# HLK-7621-ALL-KIT-V2_2.net
KiCad netlist of a schematic drawn in Altium Designer
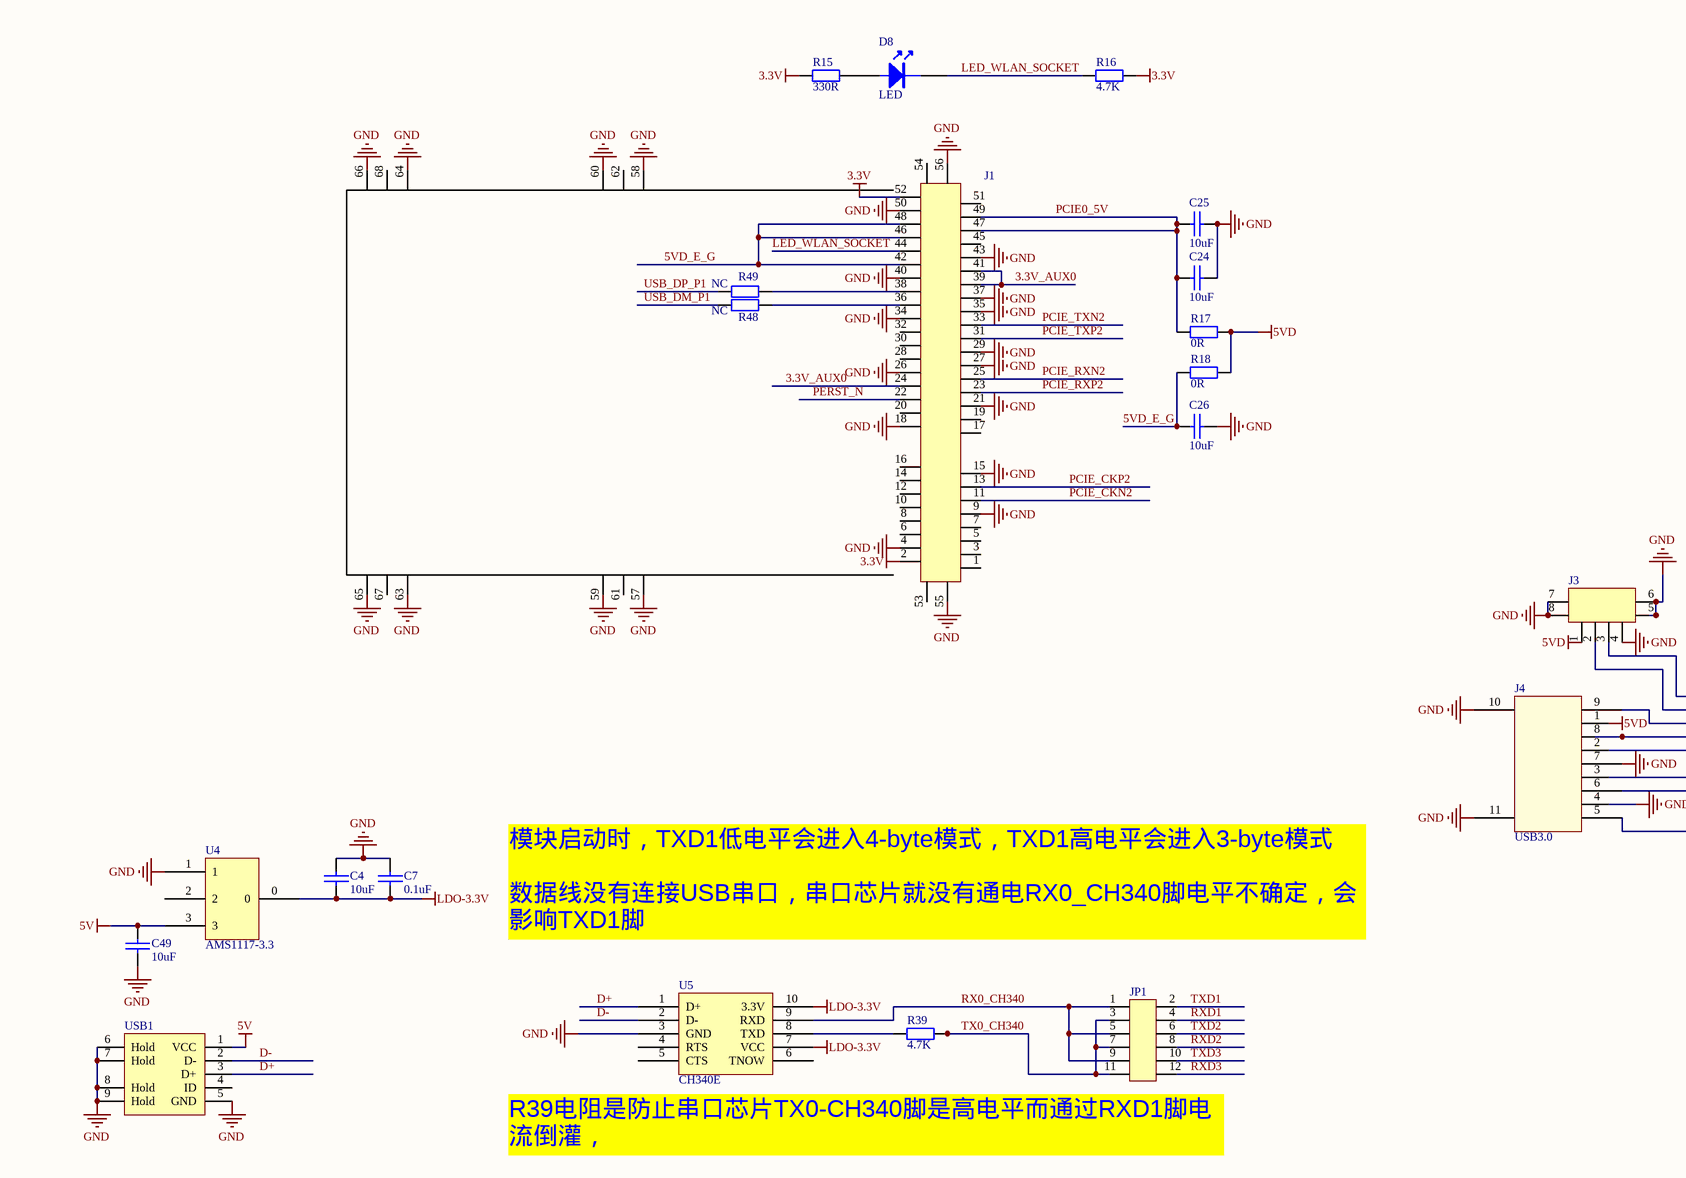
[diagram p0: HLK-7621-ALL-KIT-V2.2.SchDoc, top left]
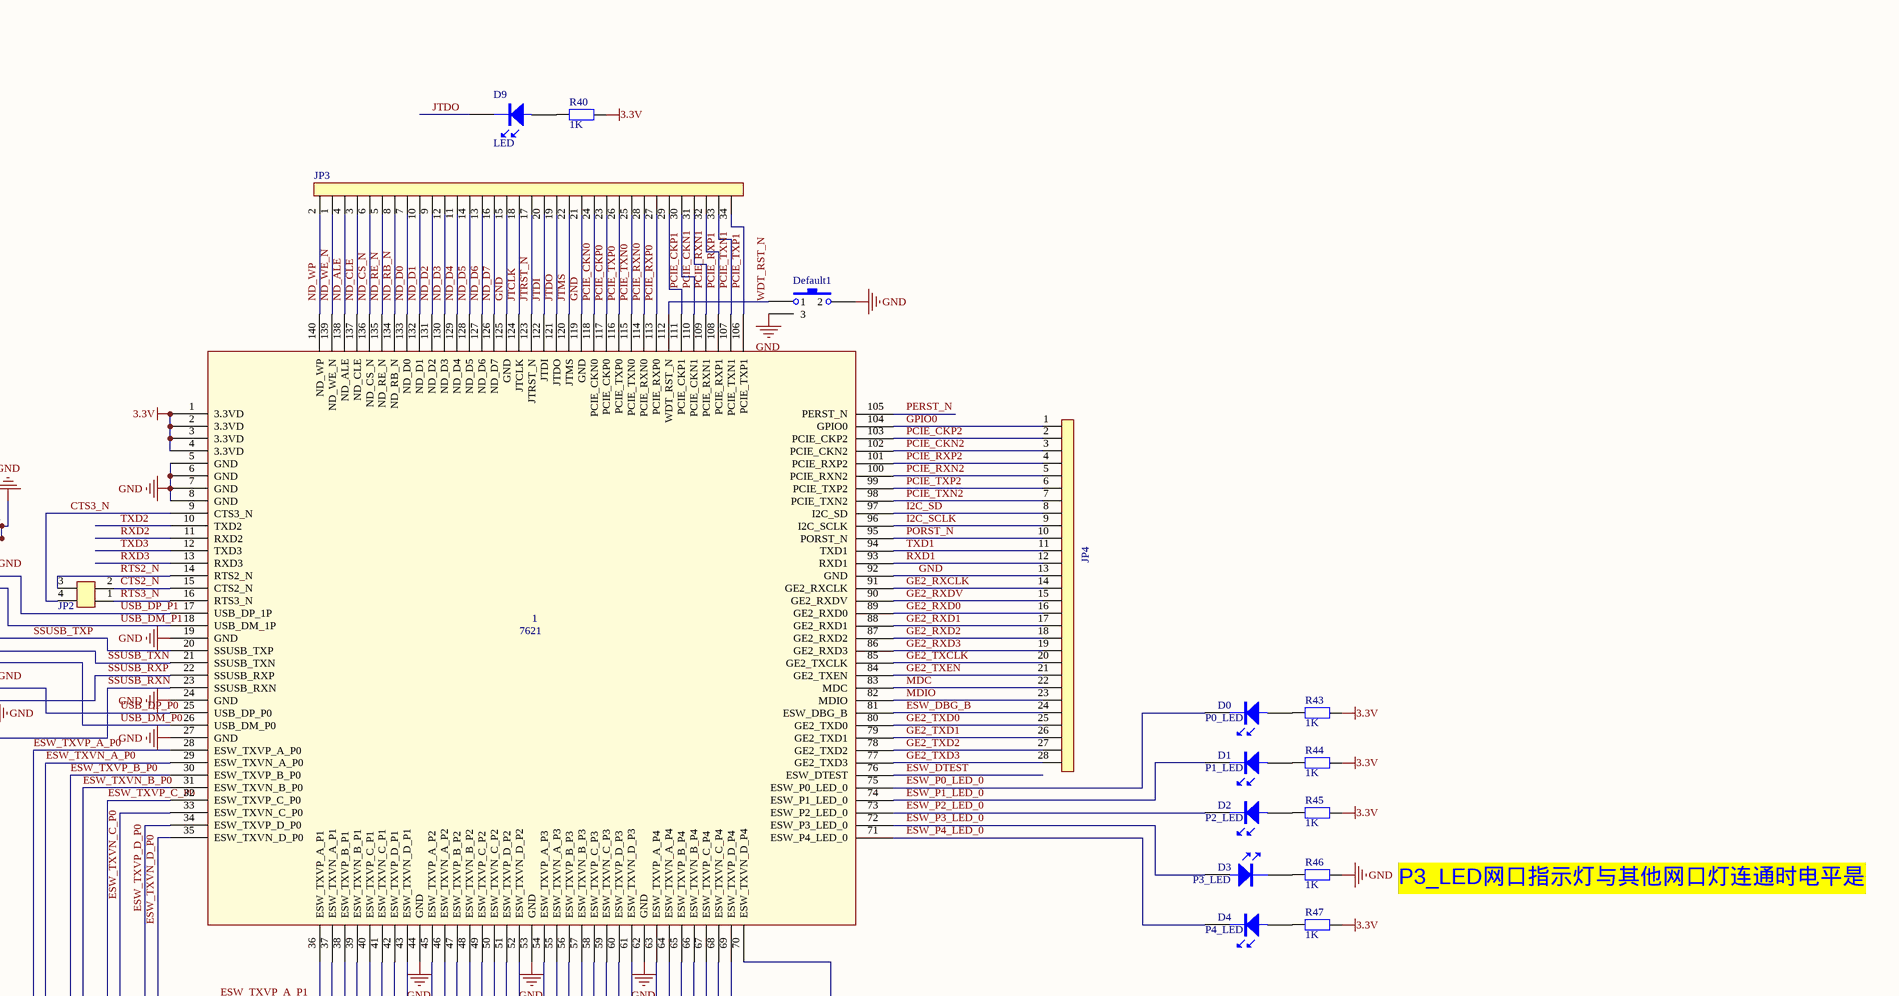
[diagram p1: HLK-7621-ALL-KIT-V2.2.SchDoc, top right]
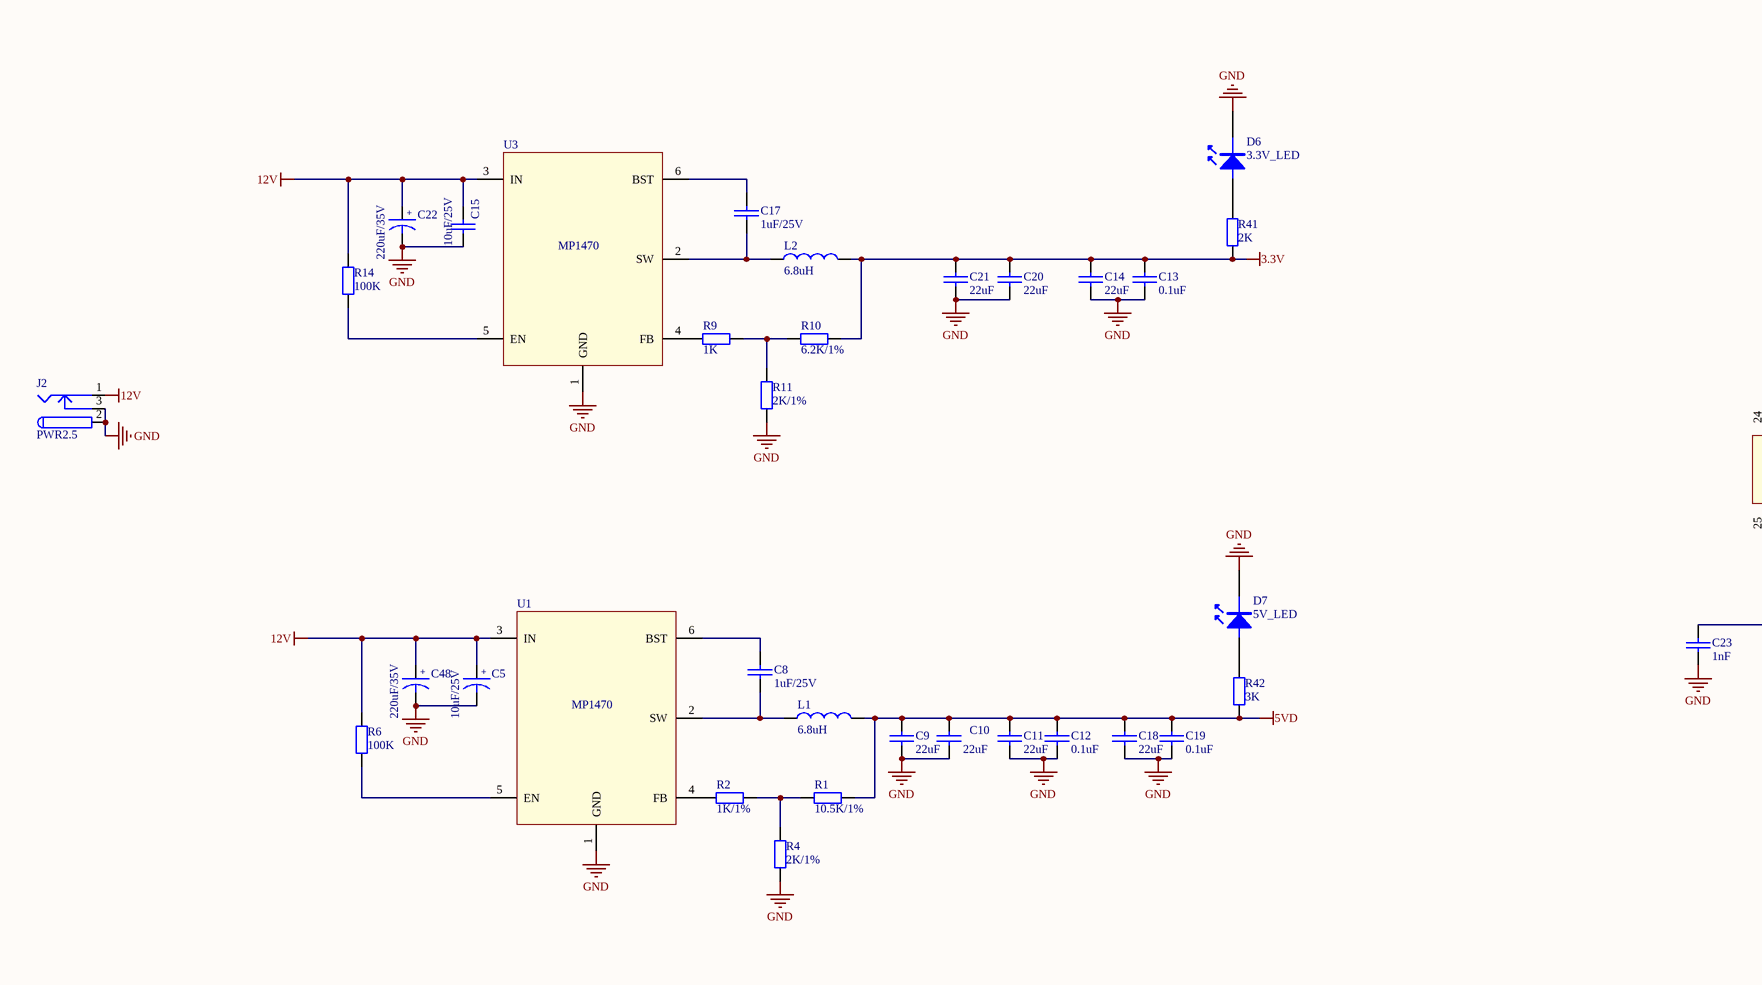
[diagram p2: HLK-7621-ALL-KIT-V2.2.SchDoc, bottom left]
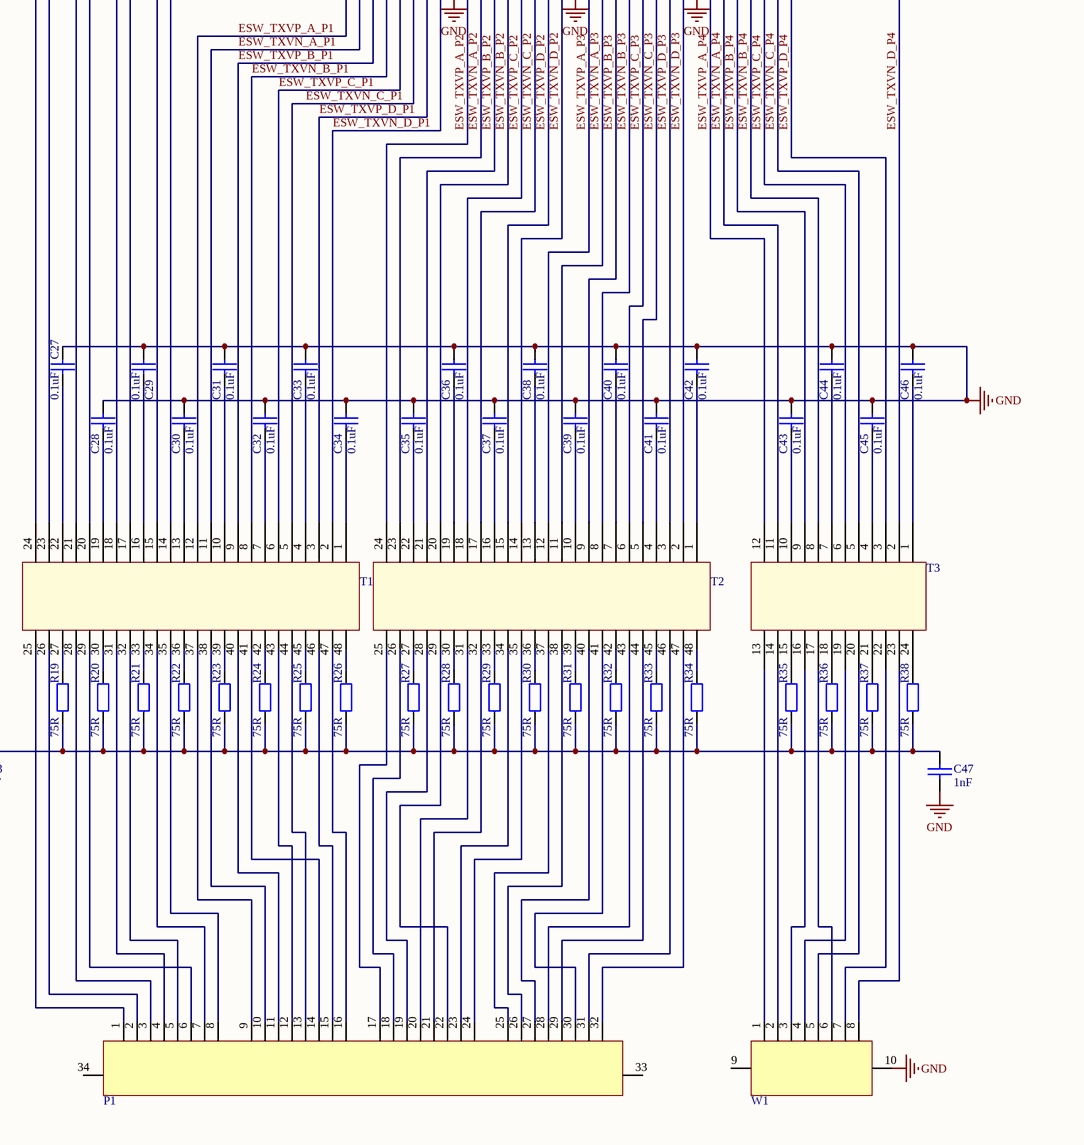
[diagram p3: HLK-7621-ALL-KIT-V2.2.SchDoc, bottom right]

(export (version "E")
  (design (tool "Eeschema 10.0.6"))
  (components
    (comp (ref "1") (value "7621") (footprint "HLK-7621") (libsource (lib "Schlib1") (part "7621")))
    (comp (ref "C4")
      (value "10uF")
      (footprint "0603")
      (description "Capacitor")
      (libsource (lib "*") (part "CAP"))
    )
    (comp (ref "C5")
      (value "10uF/25V")
      (footprint "L0805")
      (description "Capacitor")
      (libsource (lib "Miscellaneous Devices") (part "CAPACITOR POL"))
    )
    (comp (ref "C7")
      (value "0.1uF")
      (footprint "0603")
      (description "Capacitor")
      (libsource (lib "*") (part "CAP"))
    )
    (comp (ref "C8")
      (value "1uF/25V")
      (footprint "0603")
      (description "Capacitor")
      (libsource (lib "*") (part "CAP"))
    )
    (comp (ref "C9")
      (value "22uF")
      (footprint "0603")
      (description "Capacitor")
      (libsource (lib "*") (part "CAP"))
    )
    (comp (ref "C10")
      (value "22uF")
      (footprint "0603")
      (description "Capacitor")
      (libsource (lib "*") (part "CAP"))
    )
    (comp (ref "C11")
      (value "22uF")
      (footprint "0603")
      (description "Capacitor")
      (libsource (lib "*") (part "CAP"))
    )
    (comp (ref "C12")
      (value "0.1uF")
      (footprint "0603")
      (description "Capacitor")
      (libsource (lib "*") (part "CAP"))
    )
    (comp (ref "C13")
      (value "0.1uF")
      (footprint "0603")
      (description "Capacitor")
      (libsource (lib "*") (part "CAP"))
    )
    (comp (ref "C14")
      (value "22uF")
      (footprint "0603")
      (description "Capacitor")
      (libsource (lib "*") (part "CAP"))
    )
    (comp (ref "C15")
      (value "10uF/25V")
      (footprint "L0805")
      (description "Capacitor")
      (libsource (lib "*") (part "CAP"))
    )
    (comp (ref "C17")
      (value "1uF/25V")
      (footprint "0603")
      (description "Capacitor")
      (libsource (lib "*") (part "CAP"))
    )
    (comp (ref "C18")
      (value "22uF")
      (footprint "0603")
      (description "Capacitor")
      (libsource (lib "*") (part "CAP"))
    )
    (comp (ref "C19")
      (value "0.1uF")
      (footprint "0603")
      (description "Capacitor")
      (libsource (lib "*") (part "CAP"))
    )
    (comp (ref "C20")
      (value "22uF")
      (footprint "0603")
      (description "Capacitor")
      (libsource (lib "*") (part "CAP"))
    )
    (comp (ref "C21")
      (value "22uF")
      (footprint "0603")
      (description "Capacitor")
      (libsource (lib "*") (part "CAP"))
    )
    (comp (ref "C22")
      (value "220uF/35V")
      (footprint "CAP_SMT_8*10.5")
      (description "Capacitor")
      (libsource (lib "Miscellaneous Devices") (part "CAPACITOR POL"))
    )
    (comp (ref "C23")
      (value "1nF")
      (footprint "C1206")
      (description "Capacitor")
      (libsource (lib "*") (part "CAP"))
    )
    (comp (ref "C24")
      (value "10uF")
      (footprint "C1206")
      (description "Capacitor")
      (libsource (lib "*") (part "CAP"))
    )
    (comp (ref "C25")
      (value "10uF")
      (footprint "C1206")
      (description "Capacitor")
      (libsource (lib "*") (part "CAP"))
    )
    (comp (ref "C26")
      (value "10uF")
      (footprint "C1206")
      (description "Capacitor")
      (libsource (lib "*") (part "CAP"))
    )
    (comp (ref "C27")
      (value "0.1uF")
      (footprint "C0402")
      (description "Capacitor")
      (libsource (lib "*") (part "CAP"))
    )
    (comp (ref "C28")
      (value "0.1uF")
      (footprint "C0402")
      (description "Capacitor")
      (libsource (lib "*") (part "CAP"))
    )
    (comp (ref "C29")
      (value "0.1uF")
      (footprint "C0402")
      (description "Capacitor")
      (libsource (lib "*") (part "CAP"))
    )
    (comp (ref "C30")
      (value "0.1uF")
      (footprint "C0402")
      (description "Capacitor")
      (libsource (lib "*") (part "CAP"))
    )
    (comp (ref "C31")
      (value "0.1uF")
      (footprint "C0402")
      (description "Capacitor")
      (libsource (lib "*") (part "CAP"))
    )
    (comp (ref "C32")
      (value "0.1uF")
      (footprint "C0402")
      (description "Capacitor")
      (libsource (lib "*") (part "CAP"))
    )
    (comp (ref "C33")
      (value "0.1uF")
      (footprint "C0402")
      (description "Capacitor")
      (libsource (lib "*") (part "CAP"))
    )
    (comp (ref "C34")
      (value "0.1uF")
      (footprint "C0402")
      (description "Capacitor")
      (libsource (lib "*") (part "CAP"))
    )
    (comp (ref "C35")
      (value "0.1uF")
      (footprint "C0402")
      (description "Capacitor")
      (libsource (lib "*") (part "CAP"))
    )
    (comp (ref "C36")
      (value "0.1uF")
      (footprint "C0402")
      (description "Capacitor")
      (libsource (lib "*") (part "CAP"))
    )
    (comp (ref "C37")
      (value "0.1uF")
      (footprint "C0402")
      (description "Capacitor")
      (libsource (lib "*") (part "CAP"))
    )
    (comp (ref "C38")
      (value "0.1uF")
      (footprint "C0402")
      (description "Capacitor")
      (libsource (lib "*") (part "CAP"))
    )
    (comp (ref "C39")
      (value "0.1uF")
      (footprint "C0402")
      (description "Capacitor")
      (libsource (lib "*") (part "CAP"))
    )
    (comp (ref "C40")
      (value "0.1uF")
      (footprint "C0402")
      (description "Capacitor")
      (libsource (lib "*") (part "CAP"))
    )
    (comp (ref "C41")
      (value "0.1uF")
      (footprint "C0402")
      (description "Capacitor")
      (libsource (lib "*") (part "CAP"))
    )
    (comp (ref "C42")
      (value "0.1uF")
      (footprint "C0402")
      (description "Capacitor")
      (libsource (lib "*") (part "CAP"))
    )
    (comp (ref "C43")
      (value "0.1uF")
      (footprint "C0402")
      (description "Capacitor")
      (libsource (lib "*") (part "CAP"))
    )
    (comp (ref "C44")
      (value "0.1uF")
      (footprint "C0402")
      (description "Capacitor")
      (libsource (lib "*") (part "CAP"))
    )
    (comp (ref "C45")
      (value "0.1uF")
      (footprint "C0402")
      (description "Capacitor")
      (libsource (lib "*") (part "CAP"))
    )
    (comp (ref "C46")
      (value "0.1uF")
      (footprint "C0402")
      (description "Capacitor")
      (libsource (lib "*") (part "CAP"))
    )
    (comp (ref "C47")
      (value "1nF")
      (footprint "C1206")
      (description "Capacitor")
      (libsource (lib "*") (part "CAP"))
    )
    (comp (ref "C48")
      (value "220uF/35V")
      (footprint "CAP_SMT_8*10.5")
      (description "Capacitor")
      (libsource (lib "Miscellaneous Devices") (part "CAPACITOR POL"))
    )
    (comp (ref "C49")
      (value "10uF")
      (footprint "0603")
      (description "Capacitor")
      (libsource (lib "*") (part "CAP"))
    )
    (comp (ref "D0") (value "P0_LED") (footprint "0603LED") (libsource (lib "*") (part "LED")))
    (comp (ref "D1") (value "P1_LED") (footprint "0603LED") (libsource (lib "*") (part "LED")))
    (comp (ref "D2") (value "P2_LED") (footprint "0603LED") (libsource (lib "*") (part "LED")))
    (comp (ref "D3") (value "P3_LED") (footprint "0603LED") (libsource (lib "*") (part "LED")))
    (comp (ref "D4") (value "P4_LED") (footprint "0603LED") (libsource (lib "*") (part "LED")))
    (comp (ref "D6") (value "3.3V_LED") (footprint "0603LED") (libsource (lib "*") (part "LED")))
    (comp (ref "D7") (value "5V_LED") (footprint "0603LED") (libsource (lib "*") (part "LED")))
    (comp (ref "D8") (value "LED") (footprint "0603LED") (libsource (lib "") (part "LED_1")))
    (comp (ref "D9") (value "LED") (footprint "0603LED") (libsource (lib "*") (part "LED")))
    (comp (ref "Default1")
      (value "SW-PB")
      (footprint "K5")
      (description "Switch")
      (fields (field (name "PUBLISHER") "Altium Limited"))
      (libsource (lib "Miscellaneous Devices") (part "SW-PB"))
    )
    (comp (ref "J1")
      (value "~")
      (footprint "CONSG/54/MINICARD/AS0B22-S68-7F/HALF/FUL")
      (libsource (lib "Schlib1") (part "Component_1"))
    )
    (comp (ref "J2")
      (value "PWR2.5")
      (description "Low Voltage Power Supply Connector")
      (fields (field (name "PUBLISHER") "Altium Limited"))
      (libsource (lib "*") (part "PWR2.5"))
    )
    (comp (ref "J3") (value "~") (libsource (lib "") (part "2_1")))
    (comp (ref "J4") (value "USB3.0") (libsource (lib "Schlib1") (part "USB3.0/9P/DIP/MAINSUPER")))
    (comp (ref "JP1") (value "~") (footprint "HDR2X6") (libsource (lib "") (part "Component_1_1")))
    (comp (ref "JP2") (value "~") (footprint "HDR2X2") (libsource (lib "Schlib1") (part "2")))
    (comp (ref "JP3") (value "~") (footprint "HDR2X17") (libsource (lib "") (part "2_2")))
    (comp (ref "JP4") (value "2") (footprint "HDR2X17") (libsource (lib "") (part "2_3")))
    (comp (ref "L1")
      (value "6.8uH")
      (footprint "4.7uH SMD,5.8x5.2x4.5mm")
      (libsource (lib "ARM9") (part "INDUCTOR1"))
    )
    (comp (ref "L2")
      (value "6.8uH")
      (footprint "4.7uH SMD,5.8x5.2x4.5mm")
      (libsource (lib "ARM9") (part "INDUCTOR1"))
    )
    (comp (ref "P1")
      (value "Component_2")
      (footprint "PHJ8X4_N")
      (libsource (lib "Schlib1") (part "Component_2"))
    )
    (comp (ref "R1")
      (value "10.5K/1%")
      (footprint "0603")
      (description "Resistor")
      (fields (field (name "PUBLISHER") "Altium Limited"))
      (libsource (lib "Miscellaneous Devices") (part "Res2"))
    )
    (comp (ref "R2")
      (value "1K/1%")
      (footprint "0603")
      (description "Resistor")
      (fields (field (name "PUBLISHER") "Altium Limited"))
      (libsource (lib "Miscellaneous Devices") (part "Res2"))
    )
    (comp (ref "R4")
      (value "2K/1%")
      (footprint "0603")
      (description "Resistor")
      (fields (field (name "PUBLISHER") "Altium Limited"))
      (libsource (lib "") (part "Res2_2"))
    )
    (comp (ref "R6")
      (value "100K")
      (footprint "0603")
      (description "Resistor")
      (fields (field (name "PUBLISHER") "Altium Limited"))
      (libsource (lib "") (part "Res2_2"))
    )
    (comp (ref "R9")
      (value "1K")
      (footprint "0603")
      (description "Resistor")
      (fields (field (name "PUBLISHER") "Altium Limited"))
      (libsource (lib "Miscellaneous Devices") (part "Res2"))
    )
    (comp (ref "R10")
      (value "6.2K/1%")
      (footprint "0603")
      (description "Resistor")
      (fields (field (name "PUBLISHER") "Altium Limited"))
      (libsource (lib "Miscellaneous Devices") (part "Res2"))
    )
    (comp (ref "R11")
      (value "2K/1%")
      (footprint "0603")
      (description "Resistor")
      (fields (field (name "PUBLISHER") "Altium Limited"))
      (libsource (lib "") (part "Res2_2"))
    )
    (comp (ref "R14")
      (value "100K")
      (footprint "0603")
      (description "Resistor")
      (fields (field (name "PUBLISHER") "Altium Limited"))
      (libsource (lib "") (part "Res2_2"))
    )
    (comp (ref "R15")
      (value "330R")
      (footprint "0603")
      (description "Resistor")
      (fields (field (name "PUBLISHER") "Altium Limited"))
      (libsource (lib "Miscellaneous Devices") (part "Res2"))
    )
    (comp (ref "R16")
      (value "4.7K")
      (footprint "0603")
      (description "Resistor")
      (fields (field (name "PUBLISHER") "Altium Limited"))
      (libsource (lib "Miscellaneous Devices") (part "Res2"))
    )
    (comp (ref "R17")
      (value "0R")
      (footprint "L0805")
      (description "Resistor")
      (fields (field (name "PUBLISHER") "Altium Limited"))
      (libsource (lib "") (part "Res2_1"))
    )
    (comp (ref "R18")
      (value "0R")
      (footprint "R1206")
      (description "Resistor")
      (fields (field (name "PUBLISHER") "Altium Limited"))
      (libsource (lib "Miscellaneous Devices") (part "Res2"))
    )
    (comp (ref "R19")
      (value "75R")
      (footprint "R0402")
      (description "Resistor")
      (fields (field (name "PUBLISHER") "Altium Limited"))
      (libsource (lib "Schlib1") (part "Res2"))
    )
    (comp (ref "R20")
      (value "75R")
      (footprint "R0402")
      (description "Resistor")
      (fields (field (name "PUBLISHER") "Altium Limited"))
      (libsource (lib "Schlib1") (part "Res2"))
    )
    (comp (ref "R21")
      (value "75R")
      (footprint "R0402")
      (description "Resistor")
      (fields (field (name "PUBLISHER") "Altium Limited"))
      (libsource (lib "Schlib1") (part "Res2"))
    )
    (comp (ref "R22")
      (value "75R")
      (footprint "R0402")
      (description "Resistor")
      (fields (field (name "PUBLISHER") "Altium Limited"))
      (libsource (lib "Schlib1") (part "Res2"))
    )
    (comp (ref "R23")
      (value "75R")
      (footprint "R0402")
      (description "Resistor")
      (fields (field (name "PUBLISHER") "Altium Limited"))
      (libsource (lib "Schlib1") (part "Res2"))
    )
    (comp (ref "R24")
      (value "75R")
      (footprint "R0402")
      (description "Resistor")
      (fields (field (name "PUBLISHER") "Altium Limited"))
      (libsource (lib "Schlib1") (part "Res2"))
    )
    (comp (ref "R25")
      (value "75R")
      (footprint "R0402")
      (description "Resistor")
      (fields (field (name "PUBLISHER") "Altium Limited"))
      (libsource (lib "Schlib1") (part "Res2"))
    )
    (comp (ref "R26")
      (value "75R")
      (footprint "R0402")
      (description "Resistor")
      (fields (field (name "PUBLISHER") "Altium Limited"))
      (libsource (lib "Schlib1") (part "Res2"))
    )
    (comp (ref "R27")
      (value "75R")
      (footprint "R0402")
      (description "Resistor")
      (fields (field (name "PUBLISHER") "Altium Limited"))
      (libsource (lib "Schlib1") (part "Res2"))
    )
    (comp (ref "R28")
      (value "75R")
      (footprint "R0402")
      (description "Resistor")
      (fields (field (name "PUBLISHER") "Altium Limited"))
      (libsource (lib "Schlib1") (part "Res2"))
    )
    (comp (ref "R29")
      (value "75R")
      (footprint "R0402")
      (description "Resistor")
      (fields (field (name "PUBLISHER") "Altium Limited"))
      (libsource (lib "Schlib1") (part "Res2"))
    )
    (comp (ref "R30")
      (value "75R")
      (footprint "R0402")
      (description "Resistor")
      (fields (field (name "PUBLISHER") "Altium Limited"))
      (libsource (lib "Schlib1") (part "Res2"))
    )
    (comp (ref "R31")
      (value "75R")
      (footprint "R0402")
      (description "Resistor")
      (fields (field (name "PUBLISHER") "Altium Limited"))
      (libsource (lib "Schlib1") (part "Res2"))
    )
    (comp (ref "R32")
      (value "75R")
      (footprint "R0402")
      (description "Resistor")
      (fields (field (name "PUBLISHER") "Altium Limited"))
      (libsource (lib "Schlib1") (part "Res2"))
    )
    (comp (ref "R33")
      (value "75R")
      (footprint "R0402")
      (description "Resistor")
      (fields (field (name "PUBLISHER") "Altium Limited"))
      (libsource (lib "Schlib1") (part "Res2"))
    )
    (comp (ref "R34")
      (value "75R")
      (footprint "R0402")
      (description "Resistor")
      (fields (field (name "PUBLISHER") "Altium Limited"))
      (libsource (lib "Schlib1") (part "Res2"))
    )
    (comp (ref "R35")
      (value "75R")
      (footprint "R0402")
      (description "Resistor")
      (fields (field (name "PUBLISHER") "Altium Limited"))
      (libsource (lib "Schlib1") (part "Res2"))
    )
    (comp (ref "R36")
      (value "75R")
      (footprint "R0402")
      (description "Resistor")
      (fields (field (name "PUBLISHER") "Altium Limited"))
      (libsource (lib "Schlib1") (part "Res2"))
    )
    (comp (ref "R37")
      (value "75R")
      (footprint "R0402")
      (description "Resistor")
      (fields (field (name "PUBLISHER") "Altium Limited"))
      (libsource (lib "Schlib1") (part "Res2"))
    )
    (comp (ref "R38")
      (value "75R")
      (footprint "R0402")
      (description "Resistor")
      (fields (field (name "PUBLISHER") "Altium Limited"))
      (libsource (lib "Schlib1") (part "Res2"))
    )
    (comp (ref "R39")
      (value "4.7K")
      (footprint "0603")
      (description "Resistor")
      (fields (field (name "PUBLISHER") "Altium Limited"))
      (libsource (lib "") (part "Res2_1"))
    )
    (comp (ref "R40")
      (value "1K")
      (footprint "0603")
      (description "Resistor")
      (fields (field (name "PUBLISHER") "Altium Limited"))
      (libsource (lib "Miscellaneous Devices") (part "Res2"))
    )
    (comp (ref "R41")
      (value "2K")
      (footprint "0603")
      (description "Resistor")
      (fields (field (name "PUBLISHER") "Altium Limited"))
      (libsource (lib "") (part "Res2_2"))
    )
    (comp (ref "R42")
      (value "3K")
      (footprint "0603")
      (description "Resistor")
      (fields (field (name "PUBLISHER") "Altium Limited"))
      (libsource (lib "") (part "Res2_2"))
    )
    (comp (ref "R43")
      (value "1K")
      (footprint "0603")
      (description "Resistor")
      (fields (field (name "PUBLISHER") "Altium Limited"))
      (libsource (lib "Miscellaneous Devices") (part "Res2"))
    )
    (comp (ref "R44")
      (value "1K")
      (footprint "0603")
      (description "Resistor")
      (fields (field (name "PUBLISHER") "Altium Limited"))
      (libsource (lib "Miscellaneous Devices") (part "Res2"))
    )
    (comp (ref "R45")
      (value "1K")
      (footprint "0603")
      (description "Resistor")
      (fields (field (name "PUBLISHER") "Altium Limited"))
      (libsource (lib "Miscellaneous Devices") (part "Res2"))
    )
    (comp (ref "R46")
      (value "1K")
      (footprint "0603")
      (description "Resistor")
      (fields (field (name "PUBLISHER") "Altium Limited"))
      (libsource (lib "Miscellaneous Devices") (part "Res2"))
    )
    (comp (ref "R47")
      (value "1K")
      (footprint "0603")
      (description "Resistor")
      (fields (field (name "PUBLISHER") "Altium Limited"))
      (libsource (lib "Miscellaneous Devices") (part "Res2"))
    )
    (comp (ref "R48")
      (value "NC")
      (footprint "0603")
      (description "Resistor")
      (fields (field (name "PUBLISHER") "Altium Limited"))
      (libsource (lib "Miscellaneous Devices") (part "Res2"))
    )
    (comp (ref "R49")
      (value "NC")
      (footprint "0603")
      (description "Resistor")
      (fields (field (name "PUBLISHER") "Altium Limited"))
      (libsource (lib "Miscellaneous Devices") (part "Res2"))
    )
    (comp (ref "T1")
      (value "HN4824CG")
      (footprint "TRANSFORMER/48P/SMD/GS5014LF")
      (libsource (lib "Schlib1") (part "TRANSFORMER/24P/SMD/HN2429CG"))
    )
    (comp (ref "T2")
      (value "HN4824CG")
      (footprint "TRANSFORMER/48P/SMD/GS5014LF")
      (libsource (lib "Schlib1") (part "TRANSFORMER/24P/SMD/HN2429CG"))
    )
    (comp (ref "T3")
      (value "HN2409CG")
      (footprint "TRANSFORMER/24P/SMD/HN2429CG")
      (libsource (lib "") (part "TRANSFORMER/24P/SMD/HN2429CG_1"))
    )
    (comp (ref "U1") (value "MP1470") (footprint "MP1470") (libsource (lib "原理图库") (part "MP1470")))
    (comp (ref "U3") (value "MP1470") (footprint "MP1470") (libsource (lib "原理图库") (part "MP1470")))
    (comp (ref "U4") (value "AMS1117-3.3") (footprint "1117") (libsource (lib "") (part "Component_1_2")))
    (comp (ref "U5") (value "CH340E") (footprint "MSOP-10") (libsource (lib "Schlib1") (part "CH340E")))
    (comp (ref "USB1") (value "USB1") (libsource (lib "Schlib1") (part "USB-B")))
    (comp (ref "W1")
      (value "Component_3")
      (footprint "PCBComponent_1")
      (libsource (lib "Schlib1") (part "Component_3"))
    )
  )
  (nets
    (net (code "1") (name "/3.3V_AUX0") (class "Default")
      (node (ref "J1") (pin "24") (pinfunction "24_24") (pintype "passive"))
      (node (ref "J1") (pin "39") (pinfunction "39_39") (pintype "passive"))
      (node (ref "J1") (pin "41") (pinfunction "41_41") (pintype "passive"))
    )
    (net (code "2") (name "/5VD_E_G") (class "Default")
      (node (ref "C26") (pin "1") (pinfunction "1_1") (pintype "passive"))
      (node (ref "J1") (pin "42") (pinfunction "42_42") (pintype "passive"))
      (node (ref "J1") (pin "46") (pinfunction "46_46") (pintype "passive"))
      (node (ref "J1") (pin "48") (pinfunction "48_48") (pintype "passive"))
      (node (ref "R18") (pin "2") (pinfunction "2_2") (pintype "passive"))
    )
    (net (code "3") (name "/CTS2_N") (class "Default")
      (node (ref "1") (pin "15") (pinfunction "CTS2_N_15") (pintype "passive"))
      (node (ref "JP2") (pin "2") (pinfunction "2_2") (pintype "passive"))
    )
    (net (code "4") (name "/CTS3_N") (class "Default")
      (node (ref "1") (pin "9") (pinfunction "CTS3_N_9") (pintype "passive"))
      (node (ref "JP2") (pin "4") (pinfunction "4_4") (pintype "passive"))
    )
    (net (code "5") (name "/D+") (class "Default")
      (node (ref "U5") (pin "1") (pinfunction "D+_1") (pintype "passive"))
      (node (ref "USB1") (pin "3") (pinfunction "D+_3") (pintype "passive"))
    )
    (net (code "6") (name "/D-") (class "Default")
      (node (ref "U5") (pin "2") (pinfunction "D-_2") (pintype "passive"))
      (node (ref "USB1") (pin "2") (pinfunction "D-_2") (pintype "passive"))
    )
    (net (code "7") (name "/ESW_DBG_B") (class "Default")
      (node (ref "1") (pin "81") (pinfunction "ESW_DBG_B_81") (pintype "passive"))
      (node (ref "JP4") (pin "24") (pinfunction "24_24") (pintype "passive"))
    )
    (net (code "8") (name "/ESW_DTEST") (class "Default")
      (node (ref "1") (pin "76") (pinfunction "ESW_DTEST_76") (pintype "passive"))
    )
    (net (code "9") (name "/ESW_P0_LED_0") (class "Default")
      (node (ref "1") (pin "75") (pinfunction "ESW_P0_LED_0_75") (pintype "passive"))
      (node (ref "D0") (pin "2") (pinfunction "2_2") (pintype "passive"))
    )
    (net (code "10") (name "/ESW_P1_LED_0") (class "Default")
      (node (ref "1") (pin "74") (pinfunction "ESW_P1_LED_0_74") (pintype "passive"))
      (node (ref "D1") (pin "2") (pinfunction "2_2") (pintype "passive"))
    )
    (net (code "11") (name "/ESW_P2_LED_0") (class "Default")
      (node (ref "1") (pin "73") (pinfunction "ESW_P2_LED_0_73") (pintype "passive"))
      (node (ref "D2") (pin "2") (pinfunction "2_2") (pintype "passive"))
    )
    (net (code "12") (name "/ESW_P3_LED_0") (class "Default")
      (node (ref "1") (pin "72") (pinfunction "ESW_P3_LED_0_72") (pintype "passive"))
      (node (ref "D3") (pin "1") (pinfunction "1_1") (pintype "passive"))
    )
    (net (code "13") (name "/ESW_P4_LED_0") (class "Default")
      (node (ref "1") (pin "71") (pinfunction "ESW_P4_LED_0_71") (pintype "passive"))
      (node (ref "D4") (pin "2") (pinfunction "2_2") (pintype "passive"))
    )
    (net (code "14") (name "/ESW_TXVN_A_P0") (class "Default")
      (node (ref "1") (pin "29") (pinfunction "ESW_TXVN_A_P0_29") (pintype "passive"))
      (node (ref "T1") (pin "23") (pinfunction "23_23") (pintype "passive"))
    )
    (net (code "15") (name "/ESW_TXVN_A_P1") (class "Default")
      (node (ref "1") (pin "37") (pinfunction "ESW_TXVN_A_P1_37") (pintype "passive"))
      (node (ref "T1") (pin "11") (pinfunction "11_11") (pintype "passive"))
    )
    (net (code "16") (name "/ESW_TXVN_A_P2") (class "Default")
      (node (ref "1") (pin "46") (pinfunction "ESW_TXVN_A_P2_46") (pintype "passive"))
      (node (ref "T2") (pin "23") (pinfunction "23_23") (pintype "passive"))
    )
    (net (code "17") (name "/ESW_TXVN_A_P3") (class "Default")
      (node (ref "1") (pin "55") (pinfunction "ESW_TXVN_A_P3_55") (pintype "passive"))
      (node (ref "T2") (pin "11") (pinfunction "11_11") (pintype "passive"))
    )
    (net (code "18") (name "/ESW_TXVN_A_P4") (class "Default")
      (node (ref "1") (pin "64") (pinfunction "ESW_TXVN_A_P4_64") (pintype "passive"))
      (node (ref "T3") (pin "11") (pinfunction "11_11") (pintype "passive"))
    )
    (net (code "19") (name "/ESW_TXVN_B_P0") (class "Default")
      (node (ref "1") (pin "31") (pinfunction "ESW_TXVN_B_P0_31") (pintype "passive"))
      (node (ref "T1") (pin "20") (pinfunction "20_20") (pintype "passive"))
    )
    (net (code "20") (name "/ESW_TXVN_B_P1") (class "Default")
      (node (ref "1") (pin "39") (pinfunction "ESW_TXVN_B_P1_39") (pintype "passive"))
      (node (ref "T1") (pin "8") (pinfunction "8_8") (pintype "passive"))
    )
    (net (code "21") (name "/ESW_TXVN_B_P2") (class "Default")
      (node (ref "1") (pin "48") (pinfunction "ESW_TXVN_B_P2_48") (pintype "passive"))
      (node (ref "T2") (pin "20") (pinfunction "20_20") (pintype "passive"))
    )
    (net (code "22") (name "/ESW_TXVN_B_P3") (class "Default")
      (node (ref "1") (pin "57") (pinfunction "ESW_TXVN_B_P3_57") (pintype "passive"))
      (node (ref "T2") (pin "8") (pinfunction "8_8") (pintype "passive"))
    )
    (net (code "23") (name "/ESW_TXVN_B_P4") (class "Default")
      (node (ref "1") (pin "66") (pinfunction "ESW_TXVN_B_P4_66") (pintype "passive"))
      (node (ref "T3") (pin "8") (pinfunction "8_8") (pintype "passive"))
    )
    (net (code "24") (name "/ESW_TXVN_C_P0") (class "Default")
      (node (ref "1") (pin "33") (pinfunction "ESW_TXVN_C_P0_33") (pintype "passive"))
      (node (ref "T1") (pin "17") (pinfunction "17_17") (pintype "passive"))
    )
    (net (code "25") (name "/ESW_TXVN_C_P1") (class "Default")
      (node (ref "1") (pin "41") (pinfunction "ESW_TXVN_C_P1_41") (pintype "passive"))
      (node (ref "T1") (pin "5") (pinfunction "5_5") (pintype "passive"))
    )
    (net (code "26") (name "/ESW_TXVN_C_P2") (class "Default")
      (node (ref "1") (pin "50") (pinfunction "ESW_TXVN_C_P2_50") (pintype "passive"))
      (node (ref "T2") (pin "17") (pinfunction "17_17") (pintype "passive"))
    )
    (net (code "27") (name "/ESW_TXVN_C_P3") (class "Default")
      (node (ref "1") (pin "59") (pinfunction "ESW_TXVN_C_P3_59") (pintype "passive"))
      (node (ref "T2") (pin "5") (pinfunction "5_5") (pintype "passive"))
    )
    (net (code "28") (name "/ESW_TXVN_C_P4") (class "Default")
      (node (ref "1") (pin "68") (pinfunction "ESW_TXVN_C_P4_68") (pintype "passive"))
      (node (ref "T3") (pin "5") (pinfunction "5_5") (pintype "passive"))
    )
    (net (code "29") (name "/ESW_TXVN_D_P0") (class "Default")
      (node (ref "1") (pin "35") (pinfunction "ESW_TXVN_D_P0_35") (pintype "passive"))
      (node (ref "T1") (pin "14") (pinfunction "14_14") (pintype "passive"))
    )
    (net (code "30") (name "/ESW_TXVN_D_P1") (class "Default")
      (node (ref "1") (pin "43") (pinfunction "ESW_TXVN_D_P1_43") (pintype "passive"))
      (node (ref "T1") (pin "2") (pinfunction "2_2") (pintype "passive"))
    )
    (net (code "31") (name "/ESW_TXVN_D_P2") (class "Default")
      (node (ref "1") (pin "52") (pinfunction "ESW_TXVN_D_P2_52") (pintype "passive"))
      (node (ref "T2") (pin "14") (pinfunction "14_14") (pintype "passive"))
    )
    (net (code "32") (name "/ESW_TXVN_D_P3") (class "Default")
      (node (ref "1") (pin "61") (pinfunction "ESW_TXVN_D_P3_61") (pintype "passive"))
      (node (ref "T2") (pin "2") (pinfunction "2_2") (pintype "passive"))
    )
    (net (code "33") (name "/ESW_TXVN_D_P4") (class "Default")
      (node (ref "1") (pin "70") (pinfunction "ESW_TXVN_D_P4_70") (pintype "passive"))
      (node (ref "T3") (pin "2") (pinfunction "2_2") (pintype "passive"))
    )
    (net (code "34") (name "/ESW_TXVP_A_P0") (class "Default")
      (node (ref "1") (pin "28") (pinfunction "ESW_TXVP_A_P0_28") (pintype "passive"))
      (node (ref "T1") (pin "24") (pinfunction "24_24") (pintype "passive"))
    )
    (net (code "35") (name "/ESW_TXVP_A_P1") (class "Default")
      (node (ref "1") (pin "36") (pinfunction "ESW_TXVP_A_P1_36") (pintype "passive"))
      (node (ref "T1") (pin "12") (pinfunction "12_12") (pintype "passive"))
    )
    (net (code "36") (name "/ESW_TXVP_A_P2") (class "Default")
      (node (ref "1") (pin "45") (pinfunction "ESW_TXVP_A_P2_45") (pintype "passive"))
      (node (ref "T2") (pin "24") (pinfunction "24_24") (pintype "passive"))
    )
    (net (code "37") (name "/ESW_TXVP_A_P3") (class "Default")
      (node (ref "1") (pin "54") (pinfunction "ESW_TXVP_A_P3_54") (pintype "passive"))
      (node (ref "T2") (pin "12") (pinfunction "12_12") (pintype "passive"))
    )
    (net (code "38") (name "/ESW_TXVP_A_P4") (class "Default")
      (node (ref "1") (pin "63") (pinfunction "ESW_TXVP_A_P4_63") (pintype "passive"))
      (node (ref "T3") (pin "12") (pinfunction "12_12") (pintype "passive"))
    )
    (net (code "39") (name "/ESW_TXVP_B_P0") (class "Default")
      (node (ref "1") (pin "30") (pinfunction "ESW_TXVP_B_P0_30") (pintype "passive"))
      (node (ref "T1") (pin "21") (pinfunction "21_21") (pintype "passive"))
    )
    (net (code "40") (name "/ESW_TXVP_B_P1") (class "Default")
      (node (ref "1") (pin "38") (pinfunction "ESW_TXVP_B_P1_38") (pintype "passive"))
      (node (ref "T1") (pin "9") (pinfunction "9_9") (pintype "passive"))
    )
    (net (code "41") (name "/ESW_TXVP_B_P2") (class "Default")
      (node (ref "1") (pin "47") (pinfunction "ESW_TXVP_B_P2_47") (pintype "passive"))
      (node (ref "T2") (pin "21") (pinfunction "21_21") (pintype "passive"))
    )
    (net (code "42") (name "/ESW_TXVP_B_P3") (class "Default")
      (node (ref "1") (pin "56") (pinfunction "ESW_TXVP_B_P3_56") (pintype "passive"))
      (node (ref "T2") (pin "9") (pinfunction "9_9") (pintype "passive"))
    )
    (net (code "43") (name "/ESW_TXVP_B_P4") (class "Default")
      (node (ref "1") (pin "65") (pinfunction "ESW_TXVP_B_P4_65") (pintype "passive"))
      (node (ref "T3") (pin "9") (pinfunction "9_9") (pintype "passive"))
    )
    (net (code "44") (name "/ESW_TXVP_C_P0") (class "Default")
      (node (ref "1") (pin "32") (pinfunction "ESW_TXVP_C_P0_32") (pintype "passive"))
      (node (ref "T1") (pin "18") (pinfunction "18_18") (pintype "passive"))
    )
    (net (code "45") (name "/ESW_TXVP_C_P1") (class "Default")
      (node (ref "1") (pin "40") (pinfunction "ESW_TXVP_C_P1_40") (pintype "passive"))
      (node (ref "T1") (pin "6") (pinfunction "6_6") (pintype "passive"))
    )
    (net (code "46") (name "/ESW_TXVP_C_P2") (class "Default")
      (node (ref "1") (pin "49") (pinfunction "ESW_TXVP_C_P2_49") (pintype "passive"))
      (node (ref "T2") (pin "18") (pinfunction "18_18") (pintype "passive"))
    )
    (net (code "47") (name "/ESW_TXVP_C_P3") (class "Default")
      (node (ref "1") (pin "58") (pinfunction "ESW_TXVP_C_P3_58") (pintype "passive"))
      (node (ref "T2") (pin "6") (pinfunction "6_6") (pintype "passive"))
    )
    (net (code "48") (name "/ESW_TXVP_C_P4") (class "Default")
      (node (ref "1") (pin "67") (pinfunction "ESW_TXVP_C_P4_67") (pintype "passive"))
      (node (ref "T3") (pin "6") (pinfunction "6_6") (pintype "passive"))
    )
    (net (code "49") (name "/ESW_TXVP_D_P0") (class "Default")
      (node (ref "1") (pin "34") (pinfunction "ESW_TXVP_D_P0_34") (pintype "passive"))
      (node (ref "T1") (pin "15") (pinfunction "15_15") (pintype "passive"))
    )
    (net (code "50") (name "/ESW_TXVP_D_P1") (class "Default")
      (node (ref "1") (pin "42") (pinfunction "ESW_TXVP_D_P1_42") (pintype "passive"))
      (node (ref "T1") (pin "3") (pinfunction "3_3") (pintype "passive"))
    )
    (net (code "51") (name "/ESW_TXVP_D_P2") (class "Default")
      (node (ref "1") (pin "51") (pinfunction "ESW_TXVP_D_P2_51") (pintype "passive"))
      (node (ref "T2") (pin "15") (pinfunction "15_15") (pintype "passive"))
    )
    (net (code "52") (name "/ESW_TXVP_D_P3") (class "Default")
      (node (ref "1") (pin "60") (pinfunction "ESW_TXVP_D_P3_60") (pintype "passive"))
      (node (ref "T2") (pin "3") (pinfunction "3_3") (pintype "passive"))
    )
    (net (code "53") (name "/ESW_TXVP_D_P4") (class "Default")
      (node (ref "1") (pin "69") (pinfunction "ESW_TXVP_D_P4_69") (pintype "passive"))
      (node (ref "T3") (pin "3") (pinfunction "3_3") (pintype "passive"))
    )
    (net (code "54") (name "/GE2_RXCLK") (class "Default")
      (node (ref "1") (pin "91") (pinfunction "GE2_RXCLK_91") (pintype "passive"))
      (node (ref "JP4") (pin "14") (pinfunction "14_14") (pintype "passive"))
    )
    (net (code "55") (name "/GE2_RXD0") (class "Default")
      (node (ref "1") (pin "89") (pinfunction "GE2_RXD0_89") (pintype "passive"))
      (node (ref "JP4") (pin "16") (pinfunction "16_16") (pintype "passive"))
    )
    (net (code "56") (name "/GE2_RXD1") (class "Default")
      (node (ref "1") (pin "88") (pinfunction "GE2_RXD1_88") (pintype "passive"))
      (node (ref "JP4") (pin "17") (pinfunction "17_17") (pintype "passive"))
    )
    (net (code "57") (name "/GE2_RXD2") (class "Default")
      (node (ref "1") (pin "87") (pinfunction "GE2_RXD2_87") (pintype "passive"))
      (node (ref "JP4") (pin "18") (pinfunction "18_18") (pintype "passive"))
    )
    (net (code "58") (name "/GE2_RXD3") (class "Default")
      (node (ref "1") (pin "86") (pinfunction "GE2_RXD3_86") (pintype "passive"))
      (node (ref "JP4") (pin "19") (pinfunction "19_19") (pintype "passive"))
    )
    (net (code "59") (name "/GE2_RXDV") (class "Default")
      (node (ref "1") (pin "90") (pinfunction "GE2_RXDV_90") (pintype "passive"))
      (node (ref "JP4") (pin "15") (pinfunction "15_15") (pintype "passive"))
    )
    (net (code "60") (name "/GE2_TXCLK") (class "Default")
      (node (ref "1") (pin "85") (pinfunction "GE2_TXCLK_85") (pintype "passive"))
      (node (ref "JP4") (pin "20") (pinfunction "20_20") (pintype "passive"))
    )
    (net (code "61") (name "/GE2_TXD0") (class "Default")
      (node (ref "1") (pin "80") (pinfunction "GE2_TXD0_80") (pintype "passive"))
      (node (ref "JP4") (pin "25") (pinfunction "25_25") (pintype "passive"))
    )
    (net (code "62") (name "/GE2_TXD1") (class "Default")
      (node (ref "1") (pin "79") (pinfunction "GE2_TXD1_79") (pintype "passive"))
      (node (ref "JP4") (pin "26") (pinfunction "26_26") (pintype "passive"))
    )
    (net (code "63") (name "/GE2_TXD2") (class "Default")
      (node (ref "1") (pin "78") (pinfunction "GE2_TXD2_78") (pintype "passive"))
      (node (ref "JP4") (pin "27") (pinfunction "27_27") (pintype "passive"))
    )
    (net (code "64") (name "/GE2_TXD3") (class "Default")
      (node (ref "1") (pin "77") (pinfunction "GE2_TXD3_77") (pintype "passive"))
      (node (ref "JP4") (pin "28") (pinfunction "28_28") (pintype "passive"))
    )
    (net (code "65") (name "/GE2_TXEN") (class "Default")
      (node (ref "1") (pin "84") (pinfunction "GE2_TXEN_84") (pintype "passive"))
      (node (ref "JP4") (pin "21") (pinfunction "21_21") (pintype "passive"))
    )
    (net (code "66") (name "/GPIO0") (class "Default")
      (node (ref "1") (pin "104") (pinfunction "GPIO0_104") (pintype "passive"))
      (node (ref "JP4") (pin "1") (pinfunction "1_1") (pintype "passive"))
    )
    (net (code "67") (name "/I2C_SCLK") (class "Default")
      (node (ref "1") (pin "96") (pinfunction "I2C_SCLK_96") (pintype "passive"))
      (node (ref "JP4") (pin "9") (pinfunction "9_9") (pintype "passive"))
    )
    (net (code "68") (name "/I2C_SD") (class "Default")
      (node (ref "1") (pin "97") (pinfunction "I2C_SD_97") (pintype "passive"))
      (node (ref "JP4") (pin "8") (pinfunction "8_8") (pintype "passive"))
    )
    (net (code "69") (name "/JTCLK") (class "Default")
      (node (ref "1") (pin "124") (pinfunction "JTCLK_124") (pintype "passive"))
      (node (ref "JP3") (pin "18") (pinfunction "18_18") (pintype "passive"))
    )
    (net (code "70") (name "/JTDI") (class "Default")
      (node (ref "1") (pin "122") (pinfunction "JTDI_122") (pintype "passive"))
      (node (ref "JP3") (pin "20") (pinfunction "20_20") (pintype "passive"))
    )
    (net (code "71") (name "/JTDO") (class "Default")
      (node (ref "1") (pin "121") (pinfunction "JTDO_121") (pintype "passive"))
      (node (ref "D9") (pin "2") (pinfunction "2_2") (pintype "passive"))
      (node (ref "JP3") (pin "19") (pinfunction "19_19") (pintype "passive"))
    )
    (net (code "72") (name "/JTMS") (class "Default")
      (node (ref "1") (pin "120") (pinfunction "JTMS_120") (pintype "passive"))
      (node (ref "JP3") (pin "22") (pinfunction "22_22") (pintype "passive"))
    )
    (net (code "73") (name "/JTRST_N") (class "Default")
      (node (ref "1") (pin "123") (pinfunction "JTRST_N_123") (pintype "passive"))
      (node (ref "JP3") (pin "17") (pinfunction "17_17") (pintype "passive"))
    )
    (net (code "74") (name "/LED_WLAN_SOCKET") (class "Default")
      (node (ref "D8") (pin "1") (pinfunction "2_1") (pintype "passive"))
      (node (ref "J1") (pin "44") (pinfunction "44_44") (pintype "passive"))
      (node (ref "R16") (pin "2") (pinfunction "2_2") (pintype "passive"))
    )
    (net (code "75") (name "/MDC") (class "Default")
      (node (ref "1") (pin "83") (pinfunction "MDC_83") (pintype "passive"))
      (node (ref "JP4") (pin "22") (pinfunction "22_22") (pintype "passive"))
    )
    (net (code "76") (name "/MDIO") (class "Default")
      (node (ref "1") (pin "82") (pinfunction "MDIO_82") (pintype "passive"))
      (node (ref "JP4") (pin "23") (pinfunction "23_23") (pintype "passive"))
    )
    (net (code "77") (name "/ND_ALE") (class "Default")
      (node (ref "1") (pin "138") (pinfunction "ND_ALE_138") (pintype "passive"))
      (node (ref "JP3") (pin "4") (pinfunction "4_4") (pintype "passive"))
    )
    (net (code "78") (name "/ND_CLE") (class "Default")
      (node (ref "1") (pin "137") (pinfunction "ND_CLE_137") (pintype "passive"))
      (node (ref "JP3") (pin "3") (pinfunction "3_3") (pintype "passive"))
    )
    (net (code "79") (name "/ND_CS_N") (class "Default")
      (node (ref "1") (pin "136") (pinfunction "ND_CS_N_136") (pintype "passive"))
      (node (ref "JP3") (pin "6") (pinfunction "6_6") (pintype "passive"))
    )
    (net (code "80") (name "/ND_D0") (class "Default")
      (node (ref "1") (pin "133") (pinfunction "ND_D0_133") (pintype "passive"))
      (node (ref "JP3") (pin "7") (pinfunction "7_7") (pintype "passive"))
    )
    (net (code "81") (name "/ND_D1") (class "Default")
      (node (ref "1") (pin "132") (pinfunction "ND_D1_132") (pintype "passive"))
      (node (ref "JP3") (pin "10") (pinfunction "10_10") (pintype "passive"))
    )
    (net (code "82") (name "/ND_D2") (class "Default")
      (node (ref "1") (pin "131") (pinfunction "ND_D2_131") (pintype "passive"))
      (node (ref "JP3") (pin "9") (pinfunction "9_9") (pintype "passive"))
    )
    (net (code "83") (name "/ND_D3") (class "Default")
      (node (ref "1") (pin "130") (pinfunction "ND_D3_130") (pintype "passive"))
      (node (ref "JP3") (pin "12") (pinfunction "12_12") (pintype "passive"))
    )
    (net (code "84") (name "/ND_D4") (class "Default")
      (node (ref "1") (pin "129") (pinfunction "ND_D4_129") (pintype "passive"))
      (node (ref "JP3") (pin "11") (pinfunction "11_11") (pintype "passive"))
    )
    (net (code "85") (name "/ND_D5") (class "Default")
      (node (ref "1") (pin "128") (pinfunction "ND_D5_128") (pintype "passive"))
      (node (ref "JP3") (pin "14") (pinfunction "14_14") (pintype "passive"))
    )
    (net (code "86") (name "/ND_D6") (class "Default")
      (node (ref "1") (pin "127") (pinfunction "ND_D6_127") (pintype "passive"))
      (node (ref "JP3") (pin "13") (pinfunction "13_13") (pintype "passive"))
    )
    (net (code "87") (name "/ND_D7") (class "Default")
      (node (ref "1") (pin "126") (pinfunction "ND_D7_126") (pintype "passive"))
      (node (ref "JP3") (pin "16") (pinfunction "16_16") (pintype "passive"))
    )
    (net (code "88") (name "/ND_RB_N") (class "Default")
      (node (ref "1") (pin "134") (pinfunction "ND_RB_N_134") (pintype "passive"))
      (node (ref "JP3") (pin "8") (pinfunction "8_8") (pintype "passive"))
    )
    (net (code "89") (name "/ND_RE_N") (class "Default")
      (node (ref "1") (pin "135") (pinfunction "ND_RE_N_135") (pintype "passive"))
      (node (ref "JP3") (pin "5") (pinfunction "5_5") (pintype "passive"))
    )
    (net (code "90") (name "/ND_WE_N") (class "Default")
      (node (ref "1") (pin "139") (pinfunction "ND_WE_N_139") (pintype "passive"))
      (node (ref "JP3") (pin "1") (pinfunction "1_1") (pintype "passive"))
    )
    (net (code "91") (name "/ND_WP") (class "Default")
      (node (ref "1") (pin "140") (pinfunction "ND_WP_140") (pintype "passive"))
      (node (ref "JP3") (pin "2") (pinfunction "2_2") (pintype "passive"))
    )
    (net (code "92") (name "/PCIE0_5V") (class "Default")
      (node (ref "C24") (pin "1") (pinfunction "1_1") (pintype "passive"))
      (node (ref "C25") (pin "1") (pinfunction "1_1") (pintype "passive"))
      (node (ref "J1") (pin "47") (pinfunction "47_47") (pintype "passive"))
      (node (ref "J1") (pin "49") (pinfunction "49_49") (pintype "passive"))
      (node (ref "R17") (pin "1") (pinfunction "1_1") (pintype "passive"))
    )
    (net (code "93") (name "/PCIE_CKN0") (class "Default")
      (node (ref "1") (pin "118") (pinfunction "PCIE_CKN0_118") (pintype "passive"))
      (node (ref "JP3") (pin "24") (pinfunction "24_24") (pintype "passive"))
    )
    (net (code "94") (name "/PCIE_CKN1") (class "Default")
      (node (ref "1") (pin "110") (pinfunction "PCIE_CKN1_110") (pintype "passive"))
      (node (ref "JP3") (pin "30") (pinfunction "30_30") (pintype "passive"))
    )
    (net (code "95") (name "/PCIE_CKN2") (class "Default")
      (node (ref "1") (pin "102") (pinfunction "PCIE_CKN2_102") (pintype "passive"))
      (node (ref "J1") (pin "11") (pinfunction "11_11") (pintype "passive"))
      (node (ref "JP4") (pin "3") (pinfunction "3_3") (pintype "passive"))
    )
    (net (code "96") (name "/PCIE_CKP0") (class "Default")
      (node (ref "1") (pin "117") (pinfunction "PCIE_CKP0_117") (pintype "passive"))
      (node (ref "JP3") (pin "23") (pinfunction "23_23") (pintype "passive"))
    )
    (net (code "97") (name "/PCIE_CKP1") (class "Default")
      (node (ref "1") (pin "111") (pinfunction "PCIE_CKP1_111") (pintype "passive"))
      (node (ref "JP3") (pin "29") (pinfunction "29_29") (pintype "passive"))
    )
    (net (code "98") (name "/PCIE_CKP2") (class "Default")
      (node (ref "1") (pin "103") (pinfunction "PCIE_CKP2_103") (pintype "passive"))
      (node (ref "J1") (pin "13") (pinfunction "13_13") (pintype "passive"))
      (node (ref "JP4") (pin "2") (pinfunction "2_2") (pintype "passive"))
    )
    (net (code "99") (name "/PCIE_RXN0") (class "Default")
      (node (ref "1") (pin "114") (pinfunction "PCIE_RXN0_114") (pintype "passive"))
      (node (ref "JP3") (pin "28") (pinfunction "28_28") (pintype "passive"))
    )
    (net (code "100") (name "/PCIE_RXN1") (class "Default")
      (node (ref "1") (pin "109") (pinfunction "PCIE_RXN1_109") (pintype "passive"))
      (node (ref "JP3") (pin "31") (pinfunction "31_31") (pintype "passive"))
    )
    (net (code "101") (name "/PCIE_RXN2") (class "Default")
      (node (ref "1") (pin "100") (pinfunction "PCIE_RXN2_100") (pintype "passive"))
      (node (ref "J1") (pin "25") (pinfunction "25_25") (pintype "passive"))
      (node (ref "JP4") (pin "5") (pinfunction "5_5") (pintype "passive"))
    )
    (net (code "102") (name "/PCIE_RXP0") (class "Default")
      (node (ref "1") (pin "113") (pinfunction "PCIE_RXP0_113") (pintype "passive"))
      (node (ref "JP3") (pin "27") (pinfunction "27_27") (pintype "passive"))
    )
    (net (code "103") (name "/PCIE_RXP1") (class "Default")
      (node (ref "1") (pin "108") (pinfunction "PCIE_RXP1_108") (pintype "passive"))
      (node (ref "JP3") (pin "32") (pinfunction "32_32") (pintype "passive"))
    )
    (net (code "104") (name "/PCIE_RXP2") (class "Default")
      (node (ref "1") (pin "101") (pinfunction "PCIE_RXP2_101") (pintype "passive"))
      (node (ref "J1") (pin "23") (pinfunction "23_23") (pintype "passive"))
      (node (ref "JP4") (pin "4") (pinfunction "4_4") (pintype "passive"))
    )
    (net (code "105") (name "/PCIE_TXN0") (class "Default")
      (node (ref "1") (pin "115") (pinfunction "PCIE_TXN0_115") (pintype "passive"))
      (node (ref "JP3") (pin "25") (pinfunction "25_25") (pintype "passive"))
    )
    (net (code "106") (name "/PCIE_TXN1") (class "Default")
      (node (ref "1") (pin "107") (pinfunction "PCIE_TXN1_107") (pintype "passive"))
      (node (ref "JP3") (pin "33") (pinfunction "33_33") (pintype "passive"))
    )
    (net (code "107") (name "/PCIE_TXN2") (class "Default")
      (node (ref "1") (pin "98") (pinfunction "PCIE_TXN2_98") (pintype "passive"))
      (node (ref "J1") (pin "33") (pinfunction "33_33") (pintype "passive"))
      (node (ref "JP4") (pin "7") (pinfunction "7_7") (pintype "passive"))
    )
    (net (code "108") (name "/PCIE_TXP0") (class "Default")
      (node (ref "1") (pin "116") (pinfunction "PCIE_TXP0_116") (pintype "passive"))
      (node (ref "JP3") (pin "26") (pinfunction "26_26") (pintype "passive"))
    )
    (net (code "109") (name "/PCIE_TXP1") (class "Default")
      (node (ref "1") (pin "106") (pinfunction "PCIE_TXP1_106") (pintype "passive"))
      (node (ref "JP3") (pin "34") (pinfunction "34_34") (pintype "passive"))
    )
    (net (code "110") (name "/PCIE_TXP2") (class "Default")
      (node (ref "1") (pin "99") (pinfunction "PCIE_TXP2_99") (pintype "passive"))
      (node (ref "J1") (pin "31") (pinfunction "31_31") (pintype "passive"))
      (node (ref "JP4") (pin "6") (pinfunction "6_6") (pintype "passive"))
    )
    (net (code "111") (name "/PERST_N") (class "Default")
      (node (ref "1") (pin "105") (pinfunction "PERST_N_105") (pintype "passive"))
      (node (ref "J1") (pin "22") (pinfunction "22_22") (pintype "passive"))
    )
    (net (code "112") (name "/PORST_N") (class "Default")
      (node (ref "1") (pin "95") (pinfunction "PORST_N_95") (pintype "passive"))
      (node (ref "JP4") (pin "10") (pinfunction "10_10") (pintype "passive"))
    )
    (net (code "113") (name "/RTS2_N") (class "Default")
      (node (ref "1") (pin "14") (pinfunction "RTS2_N_14") (pintype "passive"))
      (node (ref "JP2") (pin "3") (pinfunction "3_3") (pintype "passive"))
    )
    (net (code "114") (name "/RTS3_N") (class "Default")
      (node (ref "1") (pin "16") (pinfunction "RTS3_N_16") (pintype "passive"))
      (node (ref "JP2") (pin "1") (pinfunction "1_1") (pintype "passive"))
    )
    (net (code "115") (name "/RX0_CH340") (class "Default")
      (node (ref "JP1") (pin "1") (pinfunction "1_1") (pintype "passive"))
      (node (ref "JP1") (pin "5") (pinfunction "5_5") (pintype "passive"))
      (node (ref "JP1") (pin "9") (pinfunction "9_9") (pintype "passive"))
      (node (ref "U5") (pin "9") (pinfunction "RXD_9") (pintype "passive"))
    )
    (net (code "116") (name "/RXD1") (class "Default")
      (node (ref "1") (pin "93") (pinfunction "RXD1_93") (pintype "passive"))
      (node (ref "JP1") (pin "4") (pinfunction "4_4") (pintype "passive"))
      (node (ref "JP4") (pin "12") (pinfunction "12_12") (pintype "passive"))
    )
    (net (code "117") (name "/RXD2") (class "Default")
      (node (ref "1") (pin "11") (pinfunction "RXD2_11") (pintype "passive"))
      (node (ref "JP1") (pin "8") (pinfunction "8_8") (pintype "passive"))
    )
    (net (code "118") (name "/RXD3") (class "Default")
      (node (ref "1") (pin "13") (pinfunction "RXD3_13") (pintype "passive"))
      (node (ref "JP1") (pin "12") (pinfunction "12_12") (pintype "passive"))
    )
    (net (code "119") (name "/SSUSB_RXN") (class "Default")
      (node (ref "1") (pin "23") (pinfunction "SSUSB_RXN_23") (pintype "passive"))
      (node (ref "J4") (pin "5") (pinfunction "5_5") (pintype "passive"))
    )
    (net (code "120") (name "/SSUSB_RXP") (class "Default")
      (node (ref "1") (pin "22") (pinfunction "SSUSB_RXP_22") (pintype "passive"))
      (node (ref "J4") (pin "6") (pinfunction "6_6") (pintype "passive"))
    )
    (net (code "121") (name "/SSUSB_TXN") (class "Default")
      (node (ref "1") (pin "21") (pinfunction "SSUSB_TXN_21") (pintype "passive"))
      (node (ref "J4") (pin "8") (pinfunction "8_8") (pintype "passive"))
    )
    (net (code "122") (name "/SSUSB_TXP") (class "Default")
      (node (ref "1") (pin "20") (pinfunction "SSUSB_TXP_20") (pintype "passive"))
      (node (ref "J4") (pin "9") (pinfunction "9_9") (pintype "passive"))
    )
    (net (code "123") (name "/TX0_CH340") (class "Default")
      (node (ref "JP1") (pin "11") (pinfunction "11_11") (pintype "passive"))
      (node (ref "JP1") (pin "3") (pinfunction "3_3") (pintype "passive"))
      (node (ref "JP1") (pin "7") (pinfunction "7_7") (pintype "passive"))
      (node (ref "R39") (pin "2") (pinfunction "2_2") (pintype "passive"))
    )
    (net (code "124") (name "/TXD1") (class "Default")
      (node (ref "1") (pin "94") (pinfunction "TXD1_94") (pintype "passive"))
      (node (ref "JP1") (pin "2") (pinfunction "2_2") (pintype "passive"))
      (node (ref "JP4") (pin "11") (pinfunction "11_11") (pintype "passive"))
    )
    (net (code "125") (name "/TXD2") (class "Default")
      (node (ref "1") (pin "10") (pinfunction "TXD2_10") (pintype "passive"))
      (node (ref "JP1") (pin "6") (pinfunction "6_6") (pintype "passive"))
    )
    (net (code "126") (name "/TXD3") (class "Default")
      (node (ref "1") (pin "12") (pinfunction "TXD3_12") (pintype "passive"))
      (node (ref "JP1") (pin "10") (pinfunction "10_10") (pintype "passive"))
    )
    (net (code "127") (name "/USB_DM_P0") (class "Default")
      (node (ref "1") (pin "26") (pinfunction "USB_DM_P0_26") (pintype "passive"))
      (node (ref "J4") (pin "2") (pinfunction "2_2") (pintype "passive"))
    )
    (net (code "128") (name "/USB_DM_P1") (class "Default")
      (node (ref "1") (pin "18") (pinfunction "USB_DM_1P_18") (pintype "passive"))
      (node (ref "J3") (pin "2") (pinfunction "2_2") (pintype "passive"))
      (node (ref "R48") (pin "2") (pinfunction "2_2") (pintype "passive"))
    )
    (net (code "129") (name "/USB_DP_P0") (class "Default")
      (node (ref "1") (pin "25") (pinfunction "USB_DP_P0_25") (pintype "passive"))
      (node (ref "J4") (pin "3") (pinfunction "3_3") (pintype "passive"))
    )
    (net (code "130") (name "/USB_DP_P1") (class "Default")
      (node (ref "1") (pin "17") (pinfunction "USB_DP_1P_17") (pintype "passive"))
      (node (ref "J3") (pin "3") (pinfunction "3_3") (pintype "passive"))
      (node (ref "R49") (pin "2") (pinfunction "2_2") (pintype "passive"))
    )
    (net (code "131") (name "/WDT_RST_N") (class "Default")
      (node (ref "1") (pin "112") (pinfunction "WDT_RST_N_112") (pintype "passive"))
      (node (ref "Default1") (pin "1") (pinfunction "1_1") (pintype "passive"))
    )
    (net (code "132") (name "3.3V") (class "Default")
      (node (ref "1") (pin "1") (pinfunction "3.3VD_1") (pintype "passive"))
      (node (ref "1") (pin "2") (pinfunction "3.3VD_2") (pintype "passive"))
      (node (ref "1") (pin "3") (pinfunction "3.3VD_3") (pintype "passive"))
      (node (ref "1") (pin "4") (pinfunction "3.3VD_4") (pintype "passive"))
      (node (ref "C13") (pin "1") (pinfunction "1_1") (pintype "passive"))
      (node (ref "C14") (pin "1") (pinfunction "1_1") (pintype "passive"))
      (node (ref "C20") (pin "1") (pinfunction "1_1") (pintype "passive"))
      (node (ref "C21") (pin "1") (pinfunction "1_1") (pintype "passive"))
      (node (ref "J1") (pin "2") (pinfunction "2_2") (pintype "passive"))
      (node (ref "J1") (pin "52") (pinfunction "52_52") (pintype "passive"))
      (node (ref "L2") (pin "2") (pinfunction "2_2") (pintype "passive"))
      (node (ref "R10") (pin "1") (pinfunction "1_1") (pintype "passive"))
      (node (ref "R15") (pin "2") (pinfunction "2_2") (pintype "passive"))
      (node (ref "R16") (pin "1") (pinfunction "1_1") (pintype "passive"))
      (node (ref "R40") (pin "1") (pinfunction "1_1") (pintype "passive"))
      (node (ref "R41") (pin "1") (pinfunction "1_1") (pintype "passive"))
      (node (ref "R43") (pin "1") (pinfunction "1_1") (pintype "passive"))
      (node (ref "R44") (pin "1") (pinfunction "1_1") (pintype "passive"))
      (node (ref "R45") (pin "1") (pinfunction "1_1") (pintype "passive"))
      (node (ref "R47") (pin "1") (pinfunction "1_1") (pintype "passive"))
    )
    (net (code "133") (name "5V") (class "Default")
      (node (ref "C49") (pin "2") (pinfunction "2_2") (pintype "passive"))
      (node (ref "U4") (pin "3") (pinfunction "3_3") (pintype "passive"))
      (node (ref "USB1") (pin "1") (pinfunction "VCC_1") (pintype "passive"))
    )
    (net (code "134") (name "5VD") (class "Default")
      (node (ref "C10") (pin "1") (pinfunction "1_1") (pintype "passive"))
      (node (ref "C11") (pin "1") (pinfunction "1_1") (pintype "passive"))
      (node (ref "C12") (pin "1") (pinfunction "1_1") (pintype "passive"))
      (node (ref "C18") (pin "1") (pinfunction "1_1") (pintype "passive"))
      (node (ref "C19") (pin "1") (pinfunction "1_1") (pintype "passive"))
      (node (ref "C9") (pin "1") (pinfunction "1_1") (pintype "passive"))
      (node (ref "J3") (pin "1") (pinfunction "1_1") (pintype "passive"))
      (node (ref "J4") (pin "1") (pinfunction "1_1") (pintype "passive"))
      (node (ref "L1") (pin "2") (pinfunction "2_2") (pintype "passive"))
      (node (ref "R1") (pin "1") (pinfunction "1_1") (pintype "passive"))
      (node (ref "R17") (pin "2") (pinfunction "2_2") (pintype "passive"))
      (node (ref "R18") (pin "1") (pinfunction "1_1") (pintype "passive"))
      (node (ref "R42") (pin "1") (pinfunction "1_1") (pintype "passive"))
    )
    (net (code "135") (name "12V") (class "Default")
      (node (ref "C15") (pin "1") (pinfunction "1_1") (pintype "passive"))
      (node (ref "C22") (pin "1") (pinfunction "1_1") (pintype "passive"))
      (node (ref "C48") (pin "1") (pinfunction "1_1") (pintype "passive"))
      (node (ref "C5") (pin "1") (pinfunction "1_1") (pintype "passive"))
      (node (ref "J2") (pin "1") (pinfunction "1_1") (pintype "power_in"))
      (node (ref "R14") (pin "2") (pinfunction "2_2") (pintype "passive"))
      (node (ref "R6") (pin "2") (pinfunction "2_2") (pintype "passive"))
      (node (ref "U1") (pin "3") (pinfunction "IN_3") (pintype "passive"))
      (node (ref "U3") (pin "3") (pinfunction "IN_3") (pintype "passive"))
    )
    (net (code "136") (name "GND") (class "Default")
      (node (ref "1") (pin "119") (pinfunction "GND_119") (pintype "passive"))
      (node (ref "1") (pin "125") (pinfunction "GND_125") (pintype "passive"))
      (node (ref "1") (pin "19") (pinfunction "GND_19") (pintype "passive"))
      (node (ref "1") (pin "24") (pinfunction "GND_24") (pintype "passive"))
      (node (ref "1") (pin "27") (pinfunction "GND_27") (pintype "passive"))
      (node (ref "1") (pin "44") (pinfunction "GND_44") (pintype "passive"))
      (node (ref "1") (pin "5") (pinfunction "GND_5") (pintype "passive"))
      (node (ref "1") (pin "53") (pinfunction "GND_53") (pintype "passive"))
      (node (ref "1") (pin "6") (pinfunction "GND_6") (pintype "passive"))
      (node (ref "1") (pin "62") (pinfunction "GND_62") (pintype "passive"))
      (node (ref "1") (pin "7") (pinfunction "GND_7") (pintype "passive"))
      (node (ref "1") (pin "8") (pinfunction "GND_8") (pintype "passive"))
      (node (ref "1") (pin "92") (pinfunction "GND_92") (pintype "passive"))
      (node (ref "C10") (pin "2") (pinfunction "2_2") (pintype "passive"))
      (node (ref "C11") (pin "2") (pinfunction "2_2") (pintype "passive"))
      (node (ref "C12") (pin "2") (pinfunction "2_2") (pintype "passive"))
      (node (ref "C13") (pin "2") (pinfunction "2_2") (pintype "passive"))
      (node (ref "C14") (pin "2") (pinfunction "2_2") (pintype "passive"))
      (node (ref "C15") (pin "2") (pinfunction "2_2") (pintype "passive"))
      (node (ref "C18") (pin "2") (pinfunction "2_2") (pintype "passive"))
      (node (ref "C19") (pin "2") (pinfunction "2_2") (pintype "passive"))
      (node (ref "C20") (pin "2") (pinfunction "2_2") (pintype "passive"))
      (node (ref "C21") (pin "2") (pinfunction "2_2") (pintype "passive"))
      (node (ref "C22") (pin "2") (pinfunction "2_2") (pintype "passive"))
      (node (ref "C23") (pin "2") (pinfunction "2_2") (pintype "passive"))
      (node (ref "C24") (pin "2") (pinfunction "2_2") (pintype "passive"))
      (node (ref "C25") (pin "2") (pinfunction "2_2") (pintype "passive"))
      (node (ref "C26") (pin "2") (pinfunction "2_2") (pintype "passive"))
      (node (ref "C27") (pin "1") (pinfunction "1_1") (pintype "passive"))
      (node (ref "C28") (pin "1") (pinfunction "1_1") (pintype "passive"))
      (node (ref "C29") (pin "1") (pinfunction "1_1") (pintype "passive"))
      (node (ref "C30") (pin "1") (pinfunction "1_1") (pintype "passive"))
      (node (ref "C31") (pin "1") (pinfunction "1_1") (pintype "passive"))
      (node (ref "C32") (pin "1") (pinfunction "1_1") (pintype "passive"))
      (node (ref "C33") (pin "1") (pinfunction "1_1") (pintype "passive"))
      (node (ref "C34") (pin "1") (pinfunction "1_1") (pintype "passive"))
      (node (ref "C35") (pin "1") (pinfunction "1_1") (pintype "passive"))
      (node (ref "C36") (pin "1") (pinfunction "1_1") (pintype "passive"))
      (node (ref "C37") (pin "1") (pinfunction "1_1") (pintype "passive"))
      (node (ref "C38") (pin "1") (pinfunction "1_1") (pintype "passive"))
      (node (ref "C39") (pin "1") (pinfunction "1_1") (pintype "passive"))
      (node (ref "C4") (pin "2") (pinfunction "2_2") (pintype "passive"))
      (node (ref "C40") (pin "1") (pinfunction "1_1") (pintype "passive"))
      (node (ref "C41") (pin "1") (pinfunction "1_1") (pintype "passive"))
      (node (ref "C42") (pin "1") (pinfunction "1_1") (pintype "passive"))
      (node (ref "C43") (pin "1") (pinfunction "1_1") (pintype "passive"))
      (node (ref "C44") (pin "1") (pinfunction "1_1") (pintype "passive"))
      (node (ref "C45") (pin "1") (pinfunction "1_1") (pintype "passive"))
      (node (ref "C46") (pin "1") (pinfunction "1_1") (pintype "passive"))
      (node (ref "C47") (pin "2") (pinfunction "2_2") (pintype "passive"))
      (node (ref "C48") (pin "2") (pinfunction "2_2") (pintype "passive"))
      (node (ref "C49") (pin "1") (pinfunction "1_1") (pintype "passive"))
      (node (ref "C5") (pin "2") (pinfunction "2_2") (pintype "passive"))
      (node (ref "C7") (pin "2") (pinfunction "2_2") (pintype "passive"))
      (node (ref "C9") (pin "2") (pinfunction "2_2") (pintype "passive"))
      (node (ref "D6") (pin "2") (pinfunction "2_2") (pintype "passive"))
      (node (ref "D7") (pin "2") (pinfunction "2_2") (pintype "passive"))
      (node (ref "Default1") (pin "2") (pinfunction "2_2") (pintype "passive"))
      (node (ref "Default1") (pin "3") (pinfunction "3_3") (pintype "passive"))
      (node (ref "J1") (pin "15") (pinfunction "15_15") (pintype "passive"))
      (node (ref "J1") (pin "18") (pinfunction "18_18") (pintype "passive"))
      (node (ref "J1") (pin "21") (pinfunction "21_21") (pintype "passive"))
      (node (ref "J1") (pin "26") (pinfunction "26_26") (pintype "passive"))
      (node (ref "J1") (pin "27") (pinfunction "27_27") (pintype "passive"))
      (node (ref "J1") (pin "29") (pinfunction "29_29") (pintype "passive"))
      (node (ref "J1") (pin "34") (pinfunction "34_34") (pintype "passive"))
      (node (ref "J1") (pin "35") (pinfunction "35_35") (pintype "passive"))
      (node (ref "J1") (pin "37") (pinfunction "37_37") (pintype "passive"))
      (node (ref "J1") (pin "4") (pinfunction "4_4") (pintype "passive"))
      (node (ref "J1") (pin "40") (pinfunction "40_40") (pintype "passive"))
      (node (ref "J1") (pin "43") (pinfunction "43_43") (pintype "passive"))
      (node (ref "J1") (pin "50") (pinfunction "50_50") (pintype "passive"))
      (node (ref "J1") (pin "55") (pinfunction "53_55") (pintype "passive"))
      (node (ref "J1") (pin "56") (pinfunction "54_56") (pintype "passive"))
      (node (ref "J1") (pin "57") (pinfunction "57_57") (pintype "passive"))
      (node (ref "J1") (pin "58") (pinfunction "58_58") (pintype "passive"))
      (node (ref "J1") (pin "59") (pinfunction "59_59") (pintype "passive"))
      (node (ref "J1") (pin "60") (pinfunction "60_60") (pintype "passive"))
      (node (ref "J1") (pin "63") (pinfunction "63_63") (pintype "passive"))
      (node (ref "J1") (pin "64") (pinfunction "64_64") (pintype "passive"))
      (node (ref "J1") (pin "65") (pinfunction "65_65") (pintype "passive"))
      (node (ref "J1") (pin "66") (pinfunction "66_66") (pintype "passive"))
      (node (ref "J1") (pin "9") (pinfunction "9_9") (pintype "passive"))
      (node (ref "J2") (pin "2") (pinfunction "2_2") (pintype "power_in"))
      (node (ref "J2") (pin "3") (pinfunction "3_3") (pintype "power_in"))
      (node (ref "J3") (pin "4") (pinfunction "4_4") (pintype "passive"))
      (node (ref "J3") (pin "5") (pinfunction "5_5") (pintype "passive"))
      (node (ref "J3") (pin "6") (pinfunction "6_6") (pintype "passive"))
      (node (ref "J3") (pin "7") (pinfunction "7_7") (pintype "passive"))
      (node (ref "J3") (pin "8") (pinfunction "8_8") (pintype "passive"))
      (node (ref "J4") (pin "10") (pinfunction "10_10") (pintype "passive"))
      (node (ref "J4") (pin "11") (pinfunction "11_11") (pintype "passive"))
      (node (ref "J4") (pin "4") (pinfunction "4_4") (pintype "passive"))
      (node (ref "J4") (pin "7") (pinfunction "7_7") (pintype "passive"))
      (node (ref "JP3") (pin "15") (pinfunction "15_15") (pintype "passive"))
      (node (ref "JP3") (pin "21") (pinfunction "21_21") (pintype "passive"))
      (node (ref "JP4") (pin "13") (pinfunction "13_13") (pintype "passive"))
      (node (ref "R11") (pin "1") (pinfunction "1_1") (pintype "passive"))
      (node (ref "R4") (pin "1") (pinfunction "1_1") (pintype "passive"))
      (node (ref "R46") (pin "1") (pinfunction "1_1") (pintype "passive"))
      (node (ref "U1") (pin "1") (pinfunction "GND_1") (pintype "passive"))
      (node (ref "U3") (pin "1") (pinfunction "GND_1") (pintype "passive"))
      (node (ref "U4") (pin "1") (pinfunction "1_1") (pintype "passive"))
      (node (ref "U5") (pin "3") (pinfunction "GND_3") (pintype "passive"))
      (node (ref "USB1") (pin "5") (pinfunction "GND_5") (pintype "passive"))
      (node (ref "USB1") (pin "6") (pinfunction "Hold_6") (pintype "passive"))
      (node (ref "USB1") (pin "7") (pinfunction "Hold_7") (pintype "passive"))
      (node (ref "USB1") (pin "8") (pinfunction "Hold_8") (pintype "passive"))
      (node (ref "USB1") (pin "9") (pinfunction "Hold_9") (pintype "passive"))
      (node (ref "W1") (pin "10") (pinfunction "10_10") (pintype "passive"))
    )
    (net (code "137") (name "LDO-3.3V") (class "Default")
      (node (ref "C4") (pin "1") (pinfunction "1_1") (pintype "passive"))
      (node (ref "C7") (pin "1") (pinfunction "1_1") (pintype "passive"))
      (node (ref "U4") (pin "0") (pinfunction "0_0") (pintype "passive"))
      (node (ref "U5") (pin "10") (pinfunction "3.3V_10") (pintype "passive"))
      (node (ref "U5") (pin "7") (pinfunction "VCC_7") (pintype "passive"))
    )
    (net (code "138") (name "Net-(C23-Pad1)") (class "Default")
      (node (ref "C23") (pin "1") (pinfunction "1_1") (pintype "passive"))
      (node (ref "C47") (pin "1") (pinfunction "1_1") (pintype "passive"))
      (node (ref "R19") (pin "1") (pinfunction "1_1") (pintype "passive"))
      (node (ref "R20") (pin "1") (pinfunction "1_1") (pintype "passive"))
      (node (ref "R21") (pin "1") (pinfunction "1_1") (pintype "passive"))
      (node (ref "R22") (pin "1") (pinfunction "1_1") (pintype "passive"))
      (node (ref "R23") (pin "1") (pinfunction "1_1") (pintype "passive"))
      (node (ref "R24") (pin "1") (pinfunction "1_1") (pintype "passive"))
      (node (ref "R25") (pin "1") (pinfunction "1_1") (pintype "passive"))
      (node (ref "R26") (pin "1") (pinfunction "1_1") (pintype "passive"))
      (node (ref "R27") (pin "1") (pinfunction "1_1") (pintype "passive"))
      (node (ref "R28") (pin "1") (pinfunction "1_1") (pintype "passive"))
      (node (ref "R29") (pin "1") (pinfunction "1_1") (pintype "passive"))
      (node (ref "R30") (pin "1") (pinfunction "1_1") (pintype "passive"))
      (node (ref "R31") (pin "1") (pinfunction "1_1") (pintype "passive"))
      (node (ref "R32") (pin "1") (pinfunction "1_1") (pintype "passive"))
      (node (ref "R33") (pin "1") (pinfunction "1_1") (pintype "passive"))
      (node (ref "R34") (pin "1") (pinfunction "1_1") (pintype "passive"))
      (node (ref "R35") (pin "1") (pinfunction "1_1") (pintype "passive"))
      (node (ref "R36") (pin "1") (pinfunction "1_1") (pintype "passive"))
      (node (ref "R37") (pin "1") (pinfunction "1_1") (pintype "passive"))
      (node (ref "R38") (pin "1") (pinfunction "1_1") (pintype "passive"))
    )
    (net (code "139") (name "Net-(C27-Pad2)") (class "Default")
      (node (ref "C27") (pin "2") (pinfunction "2_2") (pintype "passive"))
      (node (ref "T1") (pin "22") (pinfunction "22_22") (pintype "passive"))
    )
    (net (code "140") (name "Net-(C28-Pad2)") (class "Default")
      (node (ref "C28") (pin "2") (pinfunction "2_2") (pintype "passive"))
      (node (ref "T1") (pin "19") (pinfunction "19_19") (pintype "passive"))
    )
    (net (code "141") (name "Net-(C29-Pad2)") (class "Default")
      (node (ref "C29") (pin "2") (pinfunction "2_2") (pintype "passive"))
      (node (ref "T1") (pin "16") (pinfunction "16_16") (pintype "passive"))
    )
    (net (code "142") (name "Net-(C30-Pad2)") (class "Default")
      (node (ref "C30") (pin "2") (pinfunction "2_2") (pintype "passive"))
      (node (ref "T1") (pin "13") (pinfunction "13_13") (pintype "passive"))
    )
    (net (code "143") (name "Net-(C31-Pad2)") (class "Default")
      (node (ref "C31") (pin "2") (pinfunction "2_2") (pintype "passive"))
      (node (ref "T1") (pin "10") (pinfunction "10_10") (pintype "passive"))
    )
    (net (code "144") (name "Net-(C32-Pad2)") (class "Default")
      (node (ref "C32") (pin "2") (pinfunction "2_2") (pintype "passive"))
      (node (ref "T1") (pin "7") (pinfunction "7_7") (pintype "passive"))
    )
    (net (code "145") (name "Net-(C33-Pad2)") (class "Default")
      (node (ref "C33") (pin "2") (pinfunction "2_2") (pintype "passive"))
      (node (ref "T1") (pin "4") (pinfunction "4_4") (pintype "passive"))
    )
    (net (code "146") (name "Net-(C34-Pad2)") (class "Default")
      (node (ref "C34") (pin "2") (pinfunction "2_2") (pintype "passive"))
      (node (ref "T1") (pin "1") (pinfunction "1_1") (pintype "passive"))
    )
    (net (code "147") (name "Net-(C35-Pad2)") (class "Default")
      (node (ref "C35") (pin "2") (pinfunction "2_2") (pintype "passive"))
      (node (ref "T2") (pin "22") (pinfunction "22_22") (pintype "passive"))
    )
    (net (code "148") (name "Net-(C36-Pad2)") (class "Default")
      (node (ref "C36") (pin "2") (pinfunction "2_2") (pintype "passive"))
      (node (ref "T2") (pin "19") (pinfunction "19_19") (pintype "passive"))
    )
    (net (code "149") (name "Net-(C37-Pad2)") (class "Default")
      (node (ref "C37") (pin "2") (pinfunction "2_2") (pintype "passive"))
      (node (ref "T2") (pin "16") (pinfunction "16_16") (pintype "passive"))
    )
    (net (code "150") (name "Net-(C38-Pad2)") (class "Default")
      (node (ref "C38") (pin "2") (pinfunction "2_2") (pintype "passive"))
      (node (ref "T2") (pin "13") (pinfunction "13_13") (pintype "passive"))
    )
    (net (code "151") (name "Net-(C39-Pad2)") (class "Default")
      (node (ref "C39") (pin "2") (pinfunction "2_2") (pintype "passive"))
      (node (ref "T2") (pin "10") (pinfunction "10_10") (pintype "passive"))
    )
    (net (code "152") (name "Net-(C40-Pad2)") (class "Default")
      (node (ref "C40") (pin "2") (pinfunction "2_2") (pintype "passive"))
      (node (ref "T2") (pin "7") (pinfunction "7_7") (pintype "passive"))
    )
    (net (code "153") (name "Net-(C41-Pad2)") (class "Default")
      (node (ref "C41") (pin "2") (pinfunction "2_2") (pintype "passive"))
      (node (ref "T2") (pin "4") (pinfunction "4_4") (pintype "passive"))
    )
    (net (code "154") (name "Net-(C42-Pad2)") (class "Default")
      (node (ref "C42") (pin "2") (pinfunction "2_2") (pintype "passive"))
      (node (ref "T2") (pin "1") (pinfunction "1_1") (pintype "passive"))
    )
    (net (code "155") (name "Net-(C43-Pad2)") (class "Default")
      (node (ref "C43") (pin "2") (pinfunction "2_2") (pintype "passive"))
      (node (ref "T3") (pin "10") (pinfunction "10_10") (pintype "passive"))
    )
    (net (code "156") (name "Net-(C44-Pad2)") (class "Default")
      (node (ref "C44") (pin "2") (pinfunction "2_2") (pintype "passive"))
      (node (ref "T3") (pin "7") (pinfunction "7_7") (pintype "passive"))
    )
    (net (code "157") (name "Net-(C45-Pad2)") (class "Default")
      (node (ref "C45") (pin "2") (pinfunction "2_2") (pintype "passive"))
      (node (ref "T3") (pin "4") (pinfunction "4_4") (pintype "passive"))
    )
    (net (code "158") (name "Net-(C46-Pad2)") (class "Default")
      (node (ref "C46") (pin "2") (pinfunction "2_2") (pintype "passive"))
      (node (ref "T3") (pin "1") (pinfunction "1_1") (pintype "passive"))
    )
    (net (code "159") (name "Net-(D0-Pad1)") (class "Default")
      (node (ref "D0") (pin "1") (pinfunction "1_1") (pintype "passive"))
      (node (ref "R43") (pin "2") (pinfunction "2_2") (pintype "passive"))
    )
    (net (code "160") (name "Net-(D1-Pad1)") (class "Default")
      (node (ref "D1") (pin "1") (pinfunction "1_1") (pintype "passive"))
      (node (ref "R44") (pin "2") (pinfunction "2_2") (pintype "passive"))
    )
    (net (code "161") (name "Net-(D2-Pad1)") (class "Default")
      (node (ref "D2") (pin "1") (pinfunction "1_1") (pintype "passive"))
      (node (ref "R45") (pin "2") (pinfunction "2_2") (pintype "passive"))
    )
    (net (code "162") (name "Net-(D3-Pad2)") (class "Default")
      (node (ref "D3") (pin "2") (pinfunction "2_2") (pintype "passive"))
      (node (ref "R46") (pin "2") (pinfunction "2_2") (pintype "passive"))
    )
    (net (code "163") (name "Net-(D4-Pad1)") (class "Default")
      (node (ref "D4") (pin "1") (pinfunction "1_1") (pintype "passive"))
      (node (ref "R47") (pin "2") (pinfunction "2_2") (pintype "passive"))
    )
    (net (code "164") (name "Net-(D6-Pad1)") (class "Default")
      (node (ref "D6") (pin "1") (pinfunction "1_1") (pintype "passive"))
      (node (ref "R41") (pin "2") (pinfunction "2_2") (pintype "passive"))
    )
    (net (code "165") (name "Net-(D7-Pad1)") (class "Default")
      (node (ref "D7") (pin "1") (pinfunction "1_1") (pintype "passive"))
      (node (ref "R42") (pin "2") (pinfunction "2_2") (pintype "passive"))
    )
    (net (code "166") (name "Net-(D8-1)") (class "Default")
      (node (ref "D8") (pin "2") (pinfunction "1_2") (pintype "passive"))
      (node (ref "R15") (pin "1") (pinfunction "1_1") (pintype "passive"))
    )
    (net (code "167") (name "Net-(D9-Pad1)") (class "Default")
      (node (ref "D9") (pin "1") (pinfunction "1_1") (pintype "passive"))
      (node (ref "R40") (pin "2") (pinfunction "2_2") (pintype "passive"))
    )
    (net (code "168") (name "Net-(J1-Pad36)") (class "Default")
      (node (ref "J1") (pin "36") (pinfunction "36_36") (pintype "passive"))
      (node (ref "R48") (pin "1") (pinfunction "1_1") (pintype "passive"))
    )
    (net (code "169") (name "Net-(J1-Pad38)") (class "Default")
      (node (ref "J1") (pin "38") (pinfunction "38_38") (pintype "passive"))
      (node (ref "R49") (pin "1") (pinfunction "1_1") (pintype "passive"))
    )
    (net (code "170") (name "Net-(P1-Pad1)") (class "Default")
      (node (ref "P1") (pin "1") (pinfunction "1_1") (pintype "passive"))
      (node (ref "T1") (pin "25") (pinfunction "25_25") (pintype "passive"))
    )
    (net (code "171") (name "Net-(P1-Pad2)") (class "Default")
      (node (ref "P1") (pin "2") (pinfunction "2_2") (pintype "passive"))
      (node (ref "T1") (pin "26") (pinfunction "26_26") (pintype "passive"))
    )
    (net (code "172") (name "Net-(P1-Pad3)") (class "Default")
      (node (ref "P1") (pin "3") (pinfunction "3_3") (pintype "passive"))
      (node (ref "T1") (pin "28") (pinfunction "28_28") (pintype "passive"))
    )
    (net (code "173") (name "Net-(P1-Pad4)") (class "Default")
      (node (ref "P1") (pin "4") (pinfunction "4_4") (pintype "passive"))
      (node (ref "T1") (pin "31") (pinfunction "31_31") (pintype "passive"))
    )
    (net (code "174") (name "Net-(P1-Pad5)") (class "Default")
      (node (ref "P1") (pin "5") (pinfunction "5_5") (pintype "passive"))
      (node (ref "T1") (pin "32") (pinfunction "32_32") (pintype "passive"))
    )
    (net (code "175") (name "Net-(P1-Pad6)") (class "Default")
      (node (ref "P1") (pin "6") (pinfunction "6_6") (pintype "passive"))
      (node (ref "T1") (pin "29") (pinfunction "29_29") (pintype "passive"))
    )
    (net (code "176") (name "Net-(P1-Pad7)") (class "Default")
      (node (ref "P1") (pin "7") (pinfunction "7_7") (pintype "passive"))
      (node (ref "T1") (pin "34") (pinfunction "34_34") (pintype "passive"))
    )
    (net (code "177") (name "Net-(P1-Pad8)") (class "Default")
      (node (ref "P1") (pin "8") (pinfunction "8_8") (pintype "passive"))
      (node (ref "T1") (pin "35") (pinfunction "35_35") (pintype "passive"))
    )
    (net (code "178") (name "Net-(P1-Pad9)") (class "Default")
      (node (ref "P1") (pin "9") (pinfunction "9_9") (pintype "passive"))
      (node (ref "T1") (pin "37") (pinfunction "37_37") (pintype "passive"))
    )
    (net (code "179") (name "Net-(P1-Pad10)") (class "Default")
      (node (ref "P1") (pin "10") (pinfunction "10_10") (pintype "passive"))
      (node (ref "T1") (pin "38") (pinfunction "38_38") (pintype "passive"))
    )
    (net (code "180") (name "Net-(P1-Pad11)") (class "Default")
      (node (ref "P1") (pin "11") (pinfunction "11_11") (pintype "passive"))
      (node (ref "T1") (pin "40") (pinfunction "40_40") (pintype "passive"))
    )
    (net (code "181") (name "Net-(P1-Pad12)") (class "Default")
      (node (ref "P1") (pin "12") (pinfunction "12_12") (pintype "passive"))
      (node (ref "T1") (pin "43") (pinfunction "43_43") (pintype "passive"))
    )
    (net (code "182") (name "Net-(P1-Pad13)") (class "Default")
      (node (ref "P1") (pin "13") (pinfunction "13_13") (pintype "passive"))
      (node (ref "T1") (pin "44") (pinfunction "44_44") (pintype "passive"))
    )
    (net (code "183") (name "Net-(P1-Pad14)") (class "Default")
      (node (ref "P1") (pin "14") (pinfunction "14_14") (pintype "passive"))
      (node (ref "T1") (pin "41") (pinfunction "41_41") (pintype "passive"))
    )
    (net (code "184") (name "Net-(P1-Pad15)") (class "Default")
      (node (ref "P1") (pin "15") (pinfunction "15_15") (pintype "passive"))
      (node (ref "T1") (pin "46") (pinfunction "46_46") (pintype "passive"))
    )
    (net (code "185") (name "Net-(P1-Pad16)") (class "Default")
      (node (ref "P1") (pin "16") (pinfunction "16_16") (pintype "passive"))
      (node (ref "T1") (pin "47") (pinfunction "47_47") (pintype "passive"))
    )
    (net (code "186") (name "Net-(P1-Pad17)") (class "Default")
      (node (ref "P1") (pin "17") (pinfunction "17_17") (pintype "passive"))
      (node (ref "T2") (pin "25") (pinfunction "25_25") (pintype "passive"))
    )
    (net (code "187") (name "Net-(P1-Pad18)") (class "Default")
      (node (ref "P1") (pin "18") (pinfunction "18_18") (pintype "passive"))
      (node (ref "T2") (pin "26") (pinfunction "26_26") (pintype "passive"))
    )
    (net (code "188") (name "Net-(P1-Pad19)") (class "Default")
      (node (ref "P1") (pin "19") (pinfunction "19_19") (pintype "passive"))
      (node (ref "T2") (pin "28") (pinfunction "28_28") (pintype "passive"))
    )
    (net (code "189") (name "Net-(P1-Pad20)") (class "Default")
      (node (ref "P1") (pin "20") (pinfunction "20_20") (pintype "passive"))
      (node (ref "T2") (pin "31") (pinfunction "31_31") (pintype "passive"))
    )
    (net (code "190") (name "Net-(P1-Pad21)") (class "Default")
      (node (ref "P1") (pin "21") (pinfunction "21_21") (pintype "passive"))
      (node (ref "T2") (pin "32") (pinfunction "32_32") (pintype "passive"))
    )
    (net (code "191") (name "Net-(P1-Pad22)") (class "Default")
      (node (ref "P1") (pin "22") (pinfunction "22_22") (pintype "passive"))
      (node (ref "T2") (pin "29") (pinfunction "29_29") (pintype "passive"))
    )
    (net (code "192") (name "Net-(P1-Pad23)") (class "Default")
      (node (ref "P1") (pin "23") (pinfunction "23_23") (pintype "passive"))
      (node (ref "T2") (pin "34") (pinfunction "34_34") (pintype "passive"))
    )
    (net (code "193") (name "Net-(P1-Pad24)") (class "Default")
      (node (ref "P1") (pin "24") (pinfunction "24_24") (pintype "passive"))
      (node (ref "T2") (pin "35") (pinfunction "35_35") (pintype "passive"))
    )
    (net (code "194") (name "Net-(P1-Pad25)") (class "Default")
      (node (ref "P1") (pin "25") (pinfunction "25_25") (pintype "passive"))
      (node (ref "T2") (pin "37") (pinfunction "37_37") (pintype "passive"))
    )
    (net (code "195") (name "Net-(P1-Pad26)") (class "Default")
      (node (ref "P1") (pin "26") (pinfunction "26_26") (pintype "passive"))
      (node (ref "T2") (pin "38") (pinfunction "38_38") (pintype "passive"))
    )
    (net (code "196") (name "Net-(P1-Pad27)") (class "Default")
      (node (ref "P1") (pin "27") (pinfunction "27_27") (pintype "passive"))
      (node (ref "T2") (pin "40") (pinfunction "40_40") (pintype "passive"))
    )
    (net (code "197") (name "Net-(P1-Pad28)") (class "Default")
      (node (ref "P1") (pin "28") (pinfunction "28_28") (pintype "passive"))
      (node (ref "T2") (pin "43") (pinfunction "43_43") (pintype "passive"))
    )
    (net (code "198") (name "Net-(P1-Pad29)") (class "Default")
      (node (ref "P1") (pin "29") (pinfunction "29_29") (pintype "passive"))
      (node (ref "T2") (pin "44") (pinfunction "44_44") (pintype "passive"))
    )
    (net (code "199") (name "Net-(P1-Pad30)") (class "Default")
      (node (ref "P1") (pin "30") (pinfunction "30_30") (pintype "passive"))
      (node (ref "T2") (pin "41") (pinfunction "41_41") (pintype "passive"))
    )
    (net (code "200") (name "Net-(P1-Pad31)") (class "Default")
      (node (ref "P1") (pin "31") (pinfunction "31_31") (pintype "passive"))
      (node (ref "T2") (pin "46") (pinfunction "46_46") (pintype "passive"))
    )
    (net (code "201") (name "Net-(P1-Pad32)") (class "Default")
      (node (ref "P1") (pin "32") (pinfunction "32_32") (pintype "passive"))
      (node (ref "T2") (pin "47") (pinfunction "47_47") (pintype "passive"))
    )
    (net (code "202") (name "Net-(R1-Pad2)") (class "Default")
      (node (ref "R1") (pin "2") (pinfunction "2_2") (pintype "passive"))
      (node (ref "R2") (pin "1") (pinfunction "1_1") (pintype "passive"))
      (node (ref "R4") (pin "2") (pinfunction "2_2") (pintype "passive"))
    )
    (net (code "203") (name "Net-(R10-Pad2)") (class "Default")
      (node (ref "R10") (pin "2") (pinfunction "2_2") (pintype "passive"))
      (node (ref "R11") (pin "2") (pinfunction "2_2") (pintype "passive"))
      (node (ref "R9") (pin "1") (pinfunction "1_1") (pintype "passive"))
    )
    (net (code "204") (name "Net-(R19-Pad2)") (class "Default")
      (node (ref "R19") (pin "2") (pinfunction "2_2") (pintype "passive"))
      (node (ref "T1") (pin "27") (pinfunction "27_27") (pintype "passive"))
    )
    (net (code "205") (name "Net-(R20-Pad2)") (class "Default")
      (node (ref "R20") (pin "2") (pinfunction "2_2") (pintype "passive"))
      (node (ref "T1") (pin "30") (pinfunction "30_30") (pintype "passive"))
    )
    (net (code "206") (name "Net-(R21-Pad2)") (class "Default")
      (node (ref "R21") (pin "2") (pinfunction "2_2") (pintype "passive"))
      (node (ref "T1") (pin "33") (pinfunction "33_33") (pintype "passive"))
    )
    (net (code "207") (name "Net-(R22-Pad2)") (class "Default")
      (node (ref "R22") (pin "2") (pinfunction "2_2") (pintype "passive"))
      (node (ref "T1") (pin "36") (pinfunction "36_36") (pintype "passive"))
    )
    (net (code "208") (name "Net-(R23-Pad2)") (class "Default")
      (node (ref "R23") (pin "2") (pinfunction "2_2") (pintype "passive"))
      (node (ref "T1") (pin "39") (pinfunction "39_39") (pintype "passive"))
    )
    (net (code "209") (name "Net-(R24-Pad2)") (class "Default")
      (node (ref "R24") (pin "2") (pinfunction "2_2") (pintype "passive"))
      (node (ref "T1") (pin "42") (pinfunction "42_42") (pintype "passive"))
    )
    (net (code "210") (name "Net-(R25-Pad2)") (class "Default")
      (node (ref "R25") (pin "2") (pinfunction "2_2") (pintype "passive"))
      (node (ref "T1") (pin "45") (pinfunction "45_45") (pintype "passive"))
    )
    (net (code "211") (name "Net-(R26-Pad2)") (class "Default")
      (node (ref "R26") (pin "2") (pinfunction "2_2") (pintype "passive"))
      (node (ref "T1") (pin "48") (pinfunction "48_48") (pintype "passive"))
    )
    (net (code "212") (name "Net-(R27-Pad2)") (class "Default")
      (node (ref "R27") (pin "2") (pinfunction "2_2") (pintype "passive"))
      (node (ref "T2") (pin "27") (pinfunction "27_27") (pintype "passive"))
    )
    (net (code "213") (name "Net-(R28-Pad2)") (class "Default")
      (node (ref "R28") (pin "2") (pinfunction "2_2") (pintype "passive"))
      (node (ref "T2") (pin "30") (pinfunction "30_30") (pintype "passive"))
    )
    (net (code "214") (name "Net-(R29-Pad2)") (class "Default")
      (node (ref "R29") (pin "2") (pinfunction "2_2") (pintype "passive"))
      (node (ref "T2") (pin "33") (pinfunction "33_33") (pintype "passive"))
    )
    (net (code "215") (name "Net-(R30-Pad2)") (class "Default")
      (node (ref "R30") (pin "2") (pinfunction "2_2") (pintype "passive"))
      (node (ref "T2") (pin "36") (pinfunction "36_36") (pintype "passive"))
    )
    (net (code "216") (name "Net-(R31-Pad2)") (class "Default")
      (node (ref "R31") (pin "2") (pinfunction "2_2") (pintype "passive"))
      (node (ref "T2") (pin "39") (pinfunction "39_39") (pintype "passive"))
    )
    (net (code "217") (name "Net-(R32-Pad2)") (class "Default")
      (node (ref "R32") (pin "2") (pinfunction "2_2") (pintype "passive"))
      (node (ref "T2") (pin "42") (pinfunction "42_42") (pintype "passive"))
    )
    (net (code "218") (name "Net-(R33-Pad2)") (class "Default")
      (node (ref "R33") (pin "2") (pinfunction "2_2") (pintype "passive"))
      (node (ref "T2") (pin "45") (pinfunction "45_45") (pintype "passive"))
    )
    (net (code "219") (name "Net-(R34-Pad2)") (class "Default")
      (node (ref "R34") (pin "2") (pinfunction "2_2") (pintype "passive"))
      (node (ref "T2") (pin "48") (pinfunction "48_48") (pintype "passive"))
    )
    (net (code "220") (name "Net-(R35-Pad2)") (class "Default")
      (node (ref "R35") (pin "2") (pinfunction "2_2") (pintype "passive"))
      (node (ref "T3") (pin "15") (pinfunction "15_15") (pintype "passive"))
    )
    (net (code "221") (name "Net-(R36-Pad2)") (class "Default")
      (node (ref "R36") (pin "2") (pinfunction "2_2") (pintype "passive"))
      (node (ref "T3") (pin "18") (pinfunction "18_18") (pintype "passive"))
    )
    (net (code "222") (name "Net-(R37-Pad2)") (class "Default")
      (node (ref "R37") (pin "2") (pinfunction "2_2") (pintype "passive"))
      (node (ref "T3") (pin "21") (pinfunction "21_21") (pintype "passive"))
    )
    (net (code "223") (name "Net-(R38-Pad2)") (class "Default")
      (node (ref "R38") (pin "2") (pinfunction "2_2") (pintype "passive"))
      (node (ref "T3") (pin "24") (pinfunction "24_24") (pintype "passive"))
    )
    (net (code "224") (name "Net-(T3-Pad13)") (class "Default")
      (node (ref "T3") (pin "13") (pinfunction "13_13") (pintype "passive"))
      (node (ref "W1") (pin "1") (pinfunction "1_1") (pintype "passive"))
    )
    (net (code "225") (name "Net-(T3-Pad14)") (class "Default")
      (node (ref "T3") (pin "14") (pinfunction "14_14") (pintype "passive"))
      (node (ref "W1") (pin "2") (pinfunction "2_2") (pintype "passive"))
    )
    (net (code "226") (name "Net-(T3-Pad16)") (class "Default")
      (node (ref "T3") (pin "16") (pinfunction "16_16") (pintype "passive"))
      (node (ref "W1") (pin "3") (pinfunction "3_3") (pintype "passive"))
    )
    (net (code "227") (name "Net-(T3-Pad17)") (class "Default")
      (node (ref "T3") (pin "17") (pinfunction "17_17") (pintype "passive"))
      (node (ref "W1") (pin "6") (pinfunction "6_6") (pintype "passive"))
    )
    (net (code "228") (name "Net-(T3-Pad19)") (class "Default")
      (node (ref "T3") (pin "19") (pinfunction "19_19") (pintype "passive"))
      (node (ref "W1") (pin "4") (pinfunction "4_4") (pintype "passive"))
    )
    (net (code "229") (name "Net-(T3-Pad20)") (class "Default")
      (node (ref "T3") (pin "20") (pinfunction "20_20") (pintype "passive"))
      (node (ref "W1") (pin "5") (pinfunction "5_5") (pintype "passive"))
    )
    (net (code "230") (name "Net-(T3-Pad22)") (class "Default")
      (node (ref "T3") (pin "22") (pinfunction "22_22") (pintype "passive"))
      (node (ref "W1") (pin "7") (pinfunction "7_7") (pintype "passive"))
    )
    (net (code "231") (name "Net-(T3-Pad23)") (class "Default")
      (node (ref "T3") (pin "23") (pinfunction "23_23") (pintype "passive"))
      (node (ref "W1") (pin "8") (pinfunction "8_8") (pintype "passive"))
    )
    (net (code "232") (name "Net-(U1-BST)") (class "Default")
      (node (ref "C8") (pin "2") (pinfunction "2_2") (pintype "passive"))
      (node (ref "U1") (pin "6") (pinfunction "BST_6") (pintype "passive"))
    )
    (net (code "233") (name "Net-(U1-EN)") (class "Default")
      (node (ref "R6") (pin "1") (pinfunction "1_1") (pintype "passive"))
      (node (ref "U1") (pin "5") (pinfunction "EN_5") (pintype "passive"))
    )
    (net (code "234") (name "Net-(U1-FB)") (class "Default")
      (node (ref "R2") (pin "2") (pinfunction "2_2") (pintype "passive"))
      (node (ref "U1") (pin "4") (pinfunction "FB_4") (pintype "passive"))
    )
    (net (code "235") (name "Net-(U1-SW)") (class "Default")
      (node (ref "C8") (pin "1") (pinfunction "1_1") (pintype "passive"))
      (node (ref "L1") (pin "1") (pinfunction "1_1") (pintype "passive"))
      (node (ref "U1") (pin "2") (pinfunction "SW_2") (pintype "passive"))
    )
    (net (code "236") (name "Net-(U3-BST)") (class "Default")
      (node (ref "C17") (pin "2") (pinfunction "2_2") (pintype "passive"))
      (node (ref "U3") (pin "6") (pinfunction "BST_6") (pintype "passive"))
    )
    (net (code "237") (name "Net-(U3-EN)") (class "Default")
      (node (ref "R14") (pin "1") (pinfunction "1_1") (pintype "passive"))
      (node (ref "U3") (pin "5") (pinfunction "EN_5") (pintype "passive"))
    )
    (net (code "238") (name "Net-(U3-FB)") (class "Default")
      (node (ref "R9") (pin "2") (pinfunction "2_2") (pintype "passive"))
      (node (ref "U3") (pin "4") (pinfunction "FB_4") (pintype "passive"))
    )
    (net (code "239") (name "Net-(U3-SW)") (class "Default")
      (node (ref "C17") (pin "1") (pinfunction "1_1") (pintype "passive"))
      (node (ref "L2") (pin "1") (pinfunction "1_1") (pintype "passive"))
      (node (ref "U3") (pin "2") (pinfunction "SW_2") (pintype "passive"))
    )
    (net (code "240") (name "Net-(U5-TXD)") (class "Default")
      (node (ref "R39") (pin "1") (pinfunction "1_1") (pintype "passive"))
      (node (ref "U5") (pin "8") (pinfunction "TXD_8") (pintype "passive"))
    )
    (net (code "241") (name "unconnected-(J1-0-Pad1)") (class "Default")
      (node (ref "J1") (pin "1") (pinfunction "0_1") (pintype "passive"))
    )
    (net (code "242") (name "unconnected-(J1-Pad3)") (class "Default")
      (node (ref "J1") (pin "3") (pinfunction "3_3") (pintype "passive"))
    )
    (net (code "243") (name "unconnected-(J1-Pad5)") (class "Default")
      (node (ref "J1") (pin "5") (pinfunction "5_5") (pintype "passive"))
    )
    (net (code "244") (name "unconnected-(J1-Pad6)") (class "Default")
      (node (ref "J1") (pin "6") (pinfunction "6_6") (pintype "passive"))
    )
    (net (code "245") (name "unconnected-(J1-Pad7)") (class "Default")
      (node (ref "J1") (pin "7") (pinfunction "7_7") (pintype "passive"))
    )
    (net (code "246") (name "unconnected-(J1-Pad8)") (class "Default")
      (node (ref "J1") (pin "8") (pinfunction "8_8") (pintype "passive"))
    )
    (net (code "247") (name "unconnected-(J1-Pad10)") (class "Default")
      (node (ref "J1") (pin "10") (pinfunction "10_10") (pintype "passive"))
    )
    (net (code "248") (name "unconnected-(J1-Pad12)") (class "Default")
      (node (ref "J1") (pin "12") (pinfunction "12_12") (pintype "passive"))
    )
    (net (code "249") (name "unconnected-(J1-Pad14)") (class "Default")
      (node (ref "J1") (pin "14") (pinfunction "14_14") (pintype "passive"))
    )
    (net (code "250") (name "unconnected-(J1-Pad16)") (class "Default")
      (node (ref "J1") (pin "16") (pinfunction "16_16") (pintype "passive"))
    )
    (net (code "251") (name "unconnected-(J1-Pad17)") (class "Default")
      (node (ref "J1") (pin "17") (pinfunction "17_17") (pintype "passive"))
    )
    (net (code "252") (name "unconnected-(J1-Pad19)") (class "Default")
      (node (ref "J1") (pin "19") (pinfunction "19_19") (pintype "passive"))
    )
    (net (code "253") (name "unconnected-(J1-Pad20)") (class "Default")
      (node (ref "J1") (pin "20") (pinfunction "20_20") (pintype "passive"))
    )
    (net (code "254") (name "unconnected-(J1-Pad28)") (class "Default")
      (node (ref "J1") (pin "28") (pinfunction "28_28") (pintype "passive"))
    )
    (net (code "255") (name "unconnected-(J1-Pad30)") (class "Default")
      (node (ref "J1") (pin "30") (pinfunction "30_30") (pintype "passive"))
    )
    (net (code "256") (name "unconnected-(J1-Pad32)") (class "Default")
      (node (ref "J1") (pin "32") (pinfunction "32_32") (pintype "passive"))
    )
    (net (code "257") (name "unconnected-(J1-Pad45)") (class "Default")
      (node (ref "J1") (pin "45") (pinfunction "45_45") (pintype "passive"))
    )
    (net (code "258") (name "unconnected-(J1-Pad51)") (class "Default")
      (node (ref "J1") (pin "51") (pinfunction "51_51") (pintype "passive"))
    )
    (net (code "259") (name "unconnected-(J1-Pad53)") (class "Default")
      (node (ref "J1") (pin "53") (pinfunction "53_53") (pintype "passive"))
    )
    (net (code "260") (name "unconnected-(J1-Pad54)") (class "Default")
      (node (ref "J1") (pin "54") (pinfunction "54_54") (pintype "passive"))
    )
    (net (code "261") (name "unconnected-(J1-Pad61)") (class "Default")
      (node (ref "J1") (pin "61") (pinfunction "61_61") (pintype "passive"))
    )
    (net (code "262") (name "unconnected-(J1-Pad62)") (class "Default")
      (node (ref "J1") (pin "62") (pinfunction "62_62") (pintype "passive"))
    )
    (net (code "263") (name "unconnected-(J1-Pad67)") (class "Default")
      (node (ref "J1") (pin "67") (pinfunction "67_67") (pintype "passive"))
    )
    (net (code "264") (name "unconnected-(J1-Pad68)") (class "Default")
      (node (ref "J1") (pin "68") (pinfunction "68_68") (pintype "passive"))
    )
    (net (code "265") (name "unconnected-(P1-Pad33)") (class "Default")
      (node (ref "P1") (pin "33") (pinfunction "33_33") (pintype "passive"))
    )
    (net (code "266") (name "unconnected-(P1-Pad34)") (class "Default")
      (node (ref "P1") (pin "34") (pinfunction "34_34") (pintype "passive"))
    )
    (net (code "267") (name "unconnected-(U4-Pad2)") (class "Default")
      (node (ref "U4") (pin "2") (pinfunction "2_2") (pintype "passive"))
    )
    (net (code "268") (name "unconnected-(U5-CTS-Pad5)") (class "Default")
      (node (ref "U5") (pin "5") (pinfunction "CTS_5") (pintype "passive"))
    )
    (net (code "269") (name "unconnected-(U5-RTS-Pad4)") (class "Default")
      (node (ref "U5") (pin "4") (pinfunction "RTS_4") (pintype "passive"))
    )
    (net (code "270") (name "unconnected-(U5-TNOW-Pad6)") (class "Default")
      (node (ref "U5") (pin "6") (pinfunction "TNOW_6") (pintype "passive"))
    )
    (net (code "271") (name "unconnected-(USB1-ID-Pad4)") (class "Default")
      (node (ref "USB1") (pin "4") (pinfunction "ID_4") (pintype "passive"))
    )
    (net (code "272") (name "unconnected-(W1-Pad9)") (class "Default")
      (node (ref "W1") (pin "9") (pinfunction "9_9") (pintype "passive"))
    )
  )
)
